# WIXIE.net
KiCad netlist of a schematic drawn in EAGLE
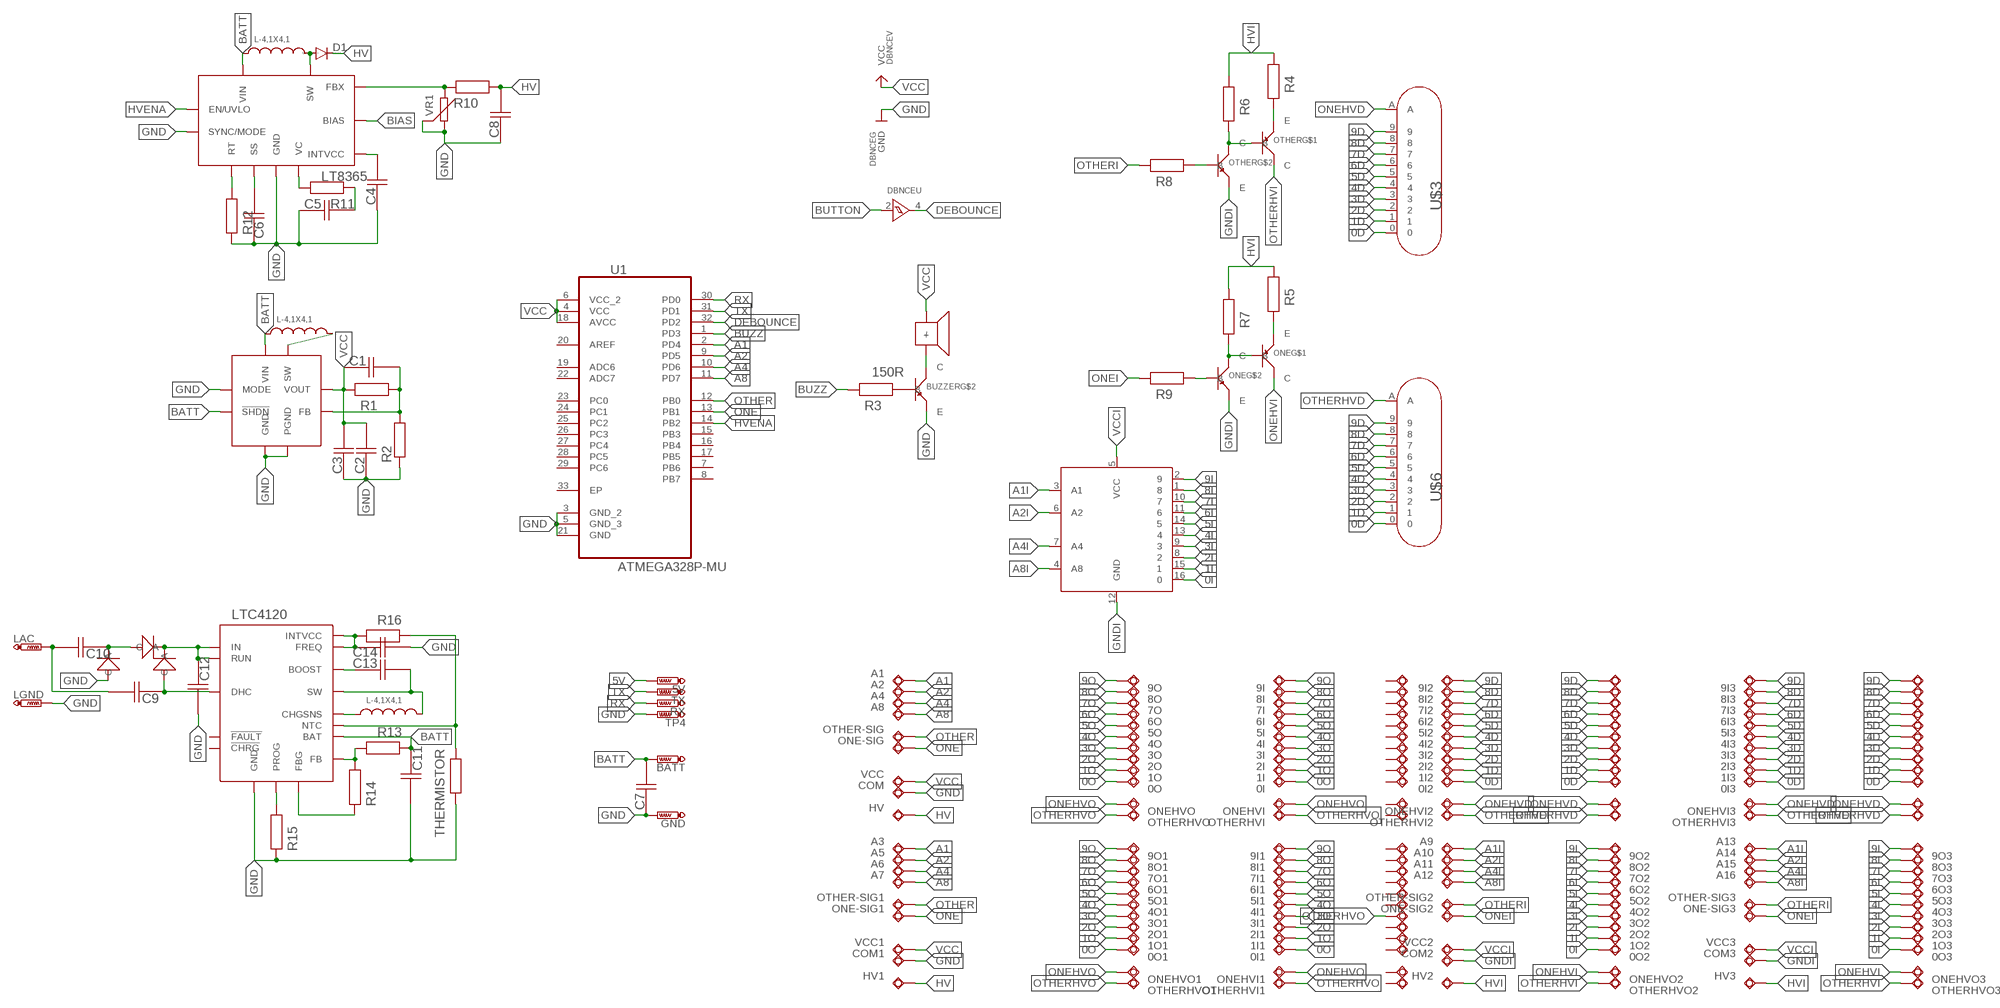
[diagram p0: schematic, sheet 1]

(export (version "E")
  (design (tool "Eeschema 10.0.6"))
  (components
    (comp (ref "0I")
      (value "TPSQTP12SQ")
      (footprint "eagle-import:TP12SQ")
      (libsource (lib "eagle-import") (part "TPSQTP12SQ"))
    )
    (comp (ref "0I1")
      (value "TPSQTP12SQ")
      (footprint "eagle-import:TP12SQ")
      (libsource (lib "eagle-import") (part "TPSQTP12SQ"))
    )
    (comp (ref "0I2")
      (value "TPSQTP12SQ")
      (footprint "eagle-import:TP12SQ")
      (libsource (lib "eagle-import") (part "TPSQTP12SQ"))
    )
    (comp (ref "0I3")
      (value "TPSQTP12SQ")
      (footprint "eagle-import:TP12SQ")
      (libsource (lib "eagle-import") (part "TPSQTP12SQ"))
    )
    (comp (ref "0O")
      (value "TPSQTP12SQ")
      (footprint "eagle-import:TP12SQ")
      (libsource (lib "eagle-import") (part "TPSQTP12SQ"))
    )
    (comp (ref "0O1")
      (value "TPSQTP12SQ")
      (footprint "eagle-import:TP12SQ")
      (libsource (lib "eagle-import") (part "TPSQTP12SQ"))
    )
    (comp (ref "0O2")
      (value "TPSQTP12SQ")
      (footprint "eagle-import:TP12SQ")
      (libsource (lib "eagle-import") (part "TPSQTP12SQ"))
    )
    (comp (ref "0O3")
      (value "TPSQTP12SQ")
      (footprint "eagle-import:TP12SQ")
      (libsource (lib "eagle-import") (part "TPSQTP12SQ"))
    )
    (comp (ref "1I")
      (value "TPSQTP12SQ")
      (footprint "eagle-import:TP12SQ")
      (libsource (lib "eagle-import") (part "TPSQTP12SQ"))
    )
    (comp (ref "1I1")
      (value "TPSQTP12SQ")
      (footprint "eagle-import:TP12SQ")
      (libsource (lib "eagle-import") (part "TPSQTP12SQ"))
    )
    (comp (ref "1I2")
      (value "TPSQTP12SQ")
      (footprint "eagle-import:TP12SQ")
      (libsource (lib "eagle-import") (part "TPSQTP12SQ"))
    )
    (comp (ref "1I3")
      (value "TPSQTP12SQ")
      (footprint "eagle-import:TP12SQ")
      (libsource (lib "eagle-import") (part "TPSQTP12SQ"))
    )
    (comp (ref "1O")
      (value "TPSQTP12SQ")
      (footprint "eagle-import:TP12SQ")
      (libsource (lib "eagle-import") (part "TPSQTP12SQ"))
    )
    (comp (ref "1O1")
      (value "TPSQTP12SQ")
      (footprint "eagle-import:TP12SQ")
      (libsource (lib "eagle-import") (part "TPSQTP12SQ"))
    )
    (comp (ref "1O2")
      (value "TPSQTP12SQ")
      (footprint "eagle-import:TP12SQ")
      (libsource (lib "eagle-import") (part "TPSQTP12SQ"))
    )
    (comp (ref "1O3")
      (value "TPSQTP12SQ")
      (footprint "eagle-import:TP12SQ")
      (libsource (lib "eagle-import") (part "TPSQTP12SQ"))
    )
    (comp (ref "2I")
      (value "TPSQTP12SQ")
      (footprint "eagle-import:TP12SQ")
      (libsource (lib "eagle-import") (part "TPSQTP12SQ"))
    )
    (comp (ref "2I1")
      (value "TPSQTP12SQ")
      (footprint "eagle-import:TP12SQ")
      (libsource (lib "eagle-import") (part "TPSQTP12SQ"))
    )
    (comp (ref "2I2")
      (value "TPSQTP12SQ")
      (footprint "eagle-import:TP12SQ")
      (libsource (lib "eagle-import") (part "TPSQTP12SQ"))
    )
    (comp (ref "2I3")
      (value "TPSQTP12SQ")
      (footprint "eagle-import:TP12SQ")
      (libsource (lib "eagle-import") (part "TPSQTP12SQ"))
    )
    (comp (ref "2O")
      (value "TPSQTP12SQ")
      (footprint "eagle-import:TP12SQ")
      (libsource (lib "eagle-import") (part "TPSQTP12SQ"))
    )
    (comp (ref "2O1")
      (value "TPSQTP12SQ")
      (footprint "eagle-import:TP12SQ")
      (libsource (lib "eagle-import") (part "TPSQTP12SQ"))
    )
    (comp (ref "2O2")
      (value "TPSQTP12SQ")
      (footprint "eagle-import:TP12SQ")
      (libsource (lib "eagle-import") (part "TPSQTP12SQ"))
    )
    (comp (ref "2O3")
      (value "TPSQTP12SQ")
      (footprint "eagle-import:TP12SQ")
      (libsource (lib "eagle-import") (part "TPSQTP12SQ"))
    )
    (comp (ref "3I")
      (value "TPSQTP12SQ")
      (footprint "eagle-import:TP12SQ")
      (libsource (lib "eagle-import") (part "TPSQTP12SQ"))
    )
    (comp (ref "3I1")
      (value "TPSQTP12SQ")
      (footprint "eagle-import:TP12SQ")
      (libsource (lib "eagle-import") (part "TPSQTP12SQ"))
    )
    (comp (ref "3I2")
      (value "TPSQTP12SQ")
      (footprint "eagle-import:TP12SQ")
      (libsource (lib "eagle-import") (part "TPSQTP12SQ"))
    )
    (comp (ref "3I3")
      (value "TPSQTP12SQ")
      (footprint "eagle-import:TP12SQ")
      (libsource (lib "eagle-import") (part "TPSQTP12SQ"))
    )
    (comp (ref "3O")
      (value "TPSQTP12SQ")
      (footprint "eagle-import:TP12SQ")
      (libsource (lib "eagle-import") (part "TPSQTP12SQ"))
    )
    (comp (ref "3O1")
      (value "TPSQTP12SQ")
      (footprint "eagle-import:TP12SQ")
      (libsource (lib "eagle-import") (part "TPSQTP12SQ"))
    )
    (comp (ref "3O2")
      (value "TPSQTP12SQ")
      (footprint "eagle-import:TP12SQ")
      (libsource (lib "eagle-import") (part "TPSQTP12SQ"))
    )
    (comp (ref "3O3")
      (value "TPSQTP12SQ")
      (footprint "eagle-import:TP12SQ")
      (libsource (lib "eagle-import") (part "TPSQTP12SQ"))
    )
    (comp (ref "4I")
      (value "TPSQTP12SQ")
      (footprint "eagle-import:TP12SQ")
      (libsource (lib "eagle-import") (part "TPSQTP12SQ"))
    )
    (comp (ref "4I1")
      (value "TPSQTP12SQ")
      (footprint "eagle-import:TP12SQ")
      (libsource (lib "eagle-import") (part "TPSQTP12SQ"))
    )
    (comp (ref "4I2")
      (value "TPSQTP12SQ")
      (footprint "eagle-import:TP12SQ")
      (libsource (lib "eagle-import") (part "TPSQTP12SQ"))
    )
    (comp (ref "4I3")
      (value "TPSQTP12SQ")
      (footprint "eagle-import:TP12SQ")
      (libsource (lib "eagle-import") (part "TPSQTP12SQ"))
    )
    (comp (ref "4O")
      (value "TPSQTP12SQ")
      (footprint "eagle-import:TP12SQ")
      (libsource (lib "eagle-import") (part "TPSQTP12SQ"))
    )
    (comp (ref "4O1")
      (value "TPSQTP12SQ")
      (footprint "eagle-import:TP12SQ")
      (libsource (lib "eagle-import") (part "TPSQTP12SQ"))
    )
    (comp (ref "4O2")
      (value "TPSQTP12SQ")
      (footprint "eagle-import:TP12SQ")
      (libsource (lib "eagle-import") (part "TPSQTP12SQ"))
    )
    (comp (ref "4O3")
      (value "TPSQTP12SQ")
      (footprint "eagle-import:TP12SQ")
      (libsource (lib "eagle-import") (part "TPSQTP12SQ"))
    )
    (comp (ref "5I")
      (value "TPSQTP12SQ")
      (footprint "eagle-import:TP12SQ")
      (libsource (lib "eagle-import") (part "TPSQTP12SQ"))
    )
    (comp (ref "5I1")
      (value "TPSQTP12SQ")
      (footprint "eagle-import:TP12SQ")
      (libsource (lib "eagle-import") (part "TPSQTP12SQ"))
    )
    (comp (ref "5I2")
      (value "TPSQTP12SQ")
      (footprint "eagle-import:TP12SQ")
      (libsource (lib "eagle-import") (part "TPSQTP12SQ"))
    )
    (comp (ref "5I3")
      (value "TPSQTP12SQ")
      (footprint "eagle-import:TP12SQ")
      (libsource (lib "eagle-import") (part "TPSQTP12SQ"))
    )
    (comp (ref "5O")
      (value "TPSQTP12SQ")
      (footprint "eagle-import:TP12SQ")
      (libsource (lib "eagle-import") (part "TPSQTP12SQ"))
    )
    (comp (ref "5O1")
      (value "TPSQTP12SQ")
      (footprint "eagle-import:TP12SQ")
      (libsource (lib "eagle-import") (part "TPSQTP12SQ"))
    )
    (comp (ref "5O2")
      (value "TPSQTP12SQ")
      (footprint "eagle-import:TP12SQ")
      (libsource (lib "eagle-import") (part "TPSQTP12SQ"))
    )
    (comp (ref "5O3")
      (value "TPSQTP12SQ")
      (footprint "eagle-import:TP12SQ")
      (libsource (lib "eagle-import") (part "TPSQTP12SQ"))
    )
    (comp (ref "5V")
      (value "PTR1B1,27")
      (footprint "eagle-import:B1,27")
      (libsource (lib "eagle-import") (part "PTR1B1,27"))
    )
    (comp (ref "6I")
      (value "TPSQTP12SQ")
      (footprint "eagle-import:TP12SQ")
      (libsource (lib "eagle-import") (part "TPSQTP12SQ"))
    )
    (comp (ref "6I1")
      (value "TPSQTP12SQ")
      (footprint "eagle-import:TP12SQ")
      (libsource (lib "eagle-import") (part "TPSQTP12SQ"))
    )
    (comp (ref "6I2")
      (value "TPSQTP12SQ")
      (footprint "eagle-import:TP12SQ")
      (libsource (lib "eagle-import") (part "TPSQTP12SQ"))
    )
    (comp (ref "6I3")
      (value "TPSQTP12SQ")
      (footprint "eagle-import:TP12SQ")
      (libsource (lib "eagle-import") (part "TPSQTP12SQ"))
    )
    (comp (ref "6O")
      (value "TPSQTP12SQ")
      (footprint "eagle-import:TP12SQ")
      (libsource (lib "eagle-import") (part "TPSQTP12SQ"))
    )
    (comp (ref "6O1")
      (value "TPSQTP12SQ")
      (footprint "eagle-import:TP12SQ")
      (libsource (lib "eagle-import") (part "TPSQTP12SQ"))
    )
    (comp (ref "6O2")
      (value "TPSQTP12SQ")
      (footprint "eagle-import:TP12SQ")
      (libsource (lib "eagle-import") (part "TPSQTP12SQ"))
    )
    (comp (ref "6O3")
      (value "TPSQTP12SQ")
      (footprint "eagle-import:TP12SQ")
      (libsource (lib "eagle-import") (part "TPSQTP12SQ"))
    )
    (comp (ref "7I")
      (value "TPSQTP12SQ")
      (footprint "eagle-import:TP12SQ")
      (libsource (lib "eagle-import") (part "TPSQTP12SQ"))
    )
    (comp (ref "7I1")
      (value "TPSQTP12SQ")
      (footprint "eagle-import:TP12SQ")
      (libsource (lib "eagle-import") (part "TPSQTP12SQ"))
    )
    (comp (ref "7I2")
      (value "TPSQTP12SQ")
      (footprint "eagle-import:TP12SQ")
      (libsource (lib "eagle-import") (part "TPSQTP12SQ"))
    )
    (comp (ref "7I3")
      (value "TPSQTP12SQ")
      (footprint "eagle-import:TP12SQ")
      (libsource (lib "eagle-import") (part "TPSQTP12SQ"))
    )
    (comp (ref "7O")
      (value "TPSQTP12SQ")
      (footprint "eagle-import:TP12SQ")
      (libsource (lib "eagle-import") (part "TPSQTP12SQ"))
    )
    (comp (ref "7O1")
      (value "TPSQTP12SQ")
      (footprint "eagle-import:TP12SQ")
      (libsource (lib "eagle-import") (part "TPSQTP12SQ"))
    )
    (comp (ref "7O2")
      (value "TPSQTP12SQ")
      (footprint "eagle-import:TP12SQ")
      (libsource (lib "eagle-import") (part "TPSQTP12SQ"))
    )
    (comp (ref "7O3")
      (value "TPSQTP12SQ")
      (footprint "eagle-import:TP12SQ")
      (libsource (lib "eagle-import") (part "TPSQTP12SQ"))
    )
    (comp (ref "8I")
      (value "TPSQTP12SQ")
      (footprint "eagle-import:TP12SQ")
      (libsource (lib "eagle-import") (part "TPSQTP12SQ"))
    )
    (comp (ref "8I1")
      (value "TPSQTP12SQ")
      (footprint "eagle-import:TP12SQ")
      (libsource (lib "eagle-import") (part "TPSQTP12SQ"))
    )
    (comp (ref "8I2")
      (value "TPSQTP12SQ")
      (footprint "eagle-import:TP12SQ")
      (libsource (lib "eagle-import") (part "TPSQTP12SQ"))
    )
    (comp (ref "8I3")
      (value "TPSQTP12SQ")
      (footprint "eagle-import:TP12SQ")
      (libsource (lib "eagle-import") (part "TPSQTP12SQ"))
    )
    (comp (ref "8O")
      (value "TPSQTP12SQ")
      (footprint "eagle-import:TP12SQ")
      (libsource (lib "eagle-import") (part "TPSQTP12SQ"))
    )
    (comp (ref "8O1")
      (value "TPSQTP12SQ")
      (footprint "eagle-import:TP12SQ")
      (libsource (lib "eagle-import") (part "TPSQTP12SQ"))
    )
    (comp (ref "8O2")
      (value "TPSQTP12SQ")
      (footprint "eagle-import:TP12SQ")
      (libsource (lib "eagle-import") (part "TPSQTP12SQ"))
    )
    (comp (ref "8O3")
      (value "TPSQTP12SQ")
      (footprint "eagle-import:TP12SQ")
      (libsource (lib "eagle-import") (part "TPSQTP12SQ"))
    )
    (comp (ref "9I")
      (value "TPSQTP12SQ")
      (footprint "eagle-import:TP12SQ")
      (libsource (lib "eagle-import") (part "TPSQTP12SQ"))
    )
    (comp (ref "9I1")
      (value "TPSQTP12SQ")
      (footprint "eagle-import:TP12SQ")
      (libsource (lib "eagle-import") (part "TPSQTP12SQ"))
    )
    (comp (ref "9I2")
      (value "TPSQTP12SQ")
      (footprint "eagle-import:TP12SQ")
      (libsource (lib "eagle-import") (part "TPSQTP12SQ"))
    )
    (comp (ref "9I3")
      (value "TPSQTP12SQ")
      (footprint "eagle-import:TP12SQ")
      (libsource (lib "eagle-import") (part "TPSQTP12SQ"))
    )
    (comp (ref "9O")
      (value "TPSQTP12SQ")
      (footprint "eagle-import:TP12SQ")
      (libsource (lib "eagle-import") (part "TPSQTP12SQ"))
    )
    (comp (ref "9O1")
      (value "TPSQTP12SQ")
      (footprint "eagle-import:TP12SQ")
      (libsource (lib "eagle-import") (part "TPSQTP12SQ"))
    )
    (comp (ref "9O2")
      (value "TPSQTP12SQ")
      (footprint "eagle-import:TP12SQ")
      (libsource (lib "eagle-import") (part "TPSQTP12SQ"))
    )
    (comp (ref "9O3")
      (value "TPSQTP12SQ")
      (footprint "eagle-import:TP12SQ")
      (libsource (lib "eagle-import") (part "TPSQTP12SQ"))
    )
    (comp (ref "A1")
      (value "TPSQTP12SQ")
      (footprint "eagle-import:TP12SQ")
      (libsource (lib "eagle-import") (part "TPSQTP12SQ"))
    )
    (comp (ref "A2")
      (value "TPSQTP12SQ")
      (footprint "eagle-import:TP12SQ")
      (libsource (lib "eagle-import") (part "TPSQTP12SQ"))
    )
    (comp (ref "A3")
      (value "TPSQTP12SQ")
      (footprint "eagle-import:TP12SQ")
      (libsource (lib "eagle-import") (part "TPSQTP12SQ"))
    )
    (comp (ref "A4")
      (value "TPSQTP12SQ")
      (footprint "eagle-import:TP12SQ")
      (libsource (lib "eagle-import") (part "TPSQTP12SQ"))
    )
    (comp (ref "A5")
      (value "TPSQTP12SQ")
      (footprint "eagle-import:TP12SQ")
      (libsource (lib "eagle-import") (part "TPSQTP12SQ"))
    )
    (comp (ref "A6")
      (value "TPSQTP12SQ")
      (footprint "eagle-import:TP12SQ")
      (libsource (lib "eagle-import") (part "TPSQTP12SQ"))
    )
    (comp (ref "A7")
      (value "TPSQTP12SQ")
      (footprint "eagle-import:TP12SQ")
      (libsource (lib "eagle-import") (part "TPSQTP12SQ"))
    )
    (comp (ref "A8")
      (value "TPSQTP12SQ")
      (footprint "eagle-import:TP12SQ")
      (libsource (lib "eagle-import") (part "TPSQTP12SQ"))
    )
    (comp (ref "A9")
      (value "TPSQTP12SQ")
      (footprint "eagle-import:TP12SQ")
      (libsource (lib "eagle-import") (part "TPSQTP12SQ"))
    )
    (comp (ref "A10")
      (value "TPSQTP12SQ")
      (footprint "eagle-import:TP12SQ")
      (libsource (lib "eagle-import") (part "TPSQTP12SQ"))
    )
    (comp (ref "A11")
      (value "TPSQTP12SQ")
      (footprint "eagle-import:TP12SQ")
      (libsource (lib "eagle-import") (part "TPSQTP12SQ"))
    )
    (comp (ref "A12")
      (value "TPSQTP12SQ")
      (footprint "eagle-import:TP12SQ")
      (libsource (lib "eagle-import") (part "TPSQTP12SQ"))
    )
    (comp (ref "A13")
      (value "TPSQTP12SQ")
      (footprint "eagle-import:TP12SQ")
      (libsource (lib "eagle-import") (part "TPSQTP12SQ"))
    )
    (comp (ref "A14")
      (value "TPSQTP12SQ")
      (footprint "eagle-import:TP12SQ")
      (libsource (lib "eagle-import") (part "TPSQTP12SQ"))
    )
    (comp (ref "A15")
      (value "TPSQTP12SQ")
      (footprint "eagle-import:TP12SQ")
      (libsource (lib "eagle-import") (part "TPSQTP12SQ"))
    )
    (comp (ref "A16")
      (value "TPSQTP12SQ")
      (footprint "eagle-import:TP12SQ")
      (libsource (lib "eagle-import") (part "TPSQTP12SQ"))
    )
    (comp (ref "BATT")
      (value "PTR1PAD1-13")
      (footprint "eagle-import:P1-13")
      (libsource (lib "eagle-import") (part "PTR1PAD1-13"))
    )
    (comp (ref "BUZZER")
      (value "MMDT5451")
      (footprint "eagle-import:SOT-363")
      (libsource (lib "eagle-import") (part "MMDT5451"))
    )
    (comp (ref "C1")
      (value "CAPACITOR-0603")
      (footprint "eagle-import:0603")
      (libsource (lib "eagle-import") (part "CAPACITOR-0603"))
    )
    (comp (ref "C2")
      (value "CAPACITOR-0603")
      (footprint "eagle-import:0603")
      (libsource (lib "eagle-import") (part "CAPACITOR-0603"))
    )
    (comp (ref "C3")
      (value "CAPACITOR-0603")
      (footprint "eagle-import:0603")
      (libsource (lib "eagle-import") (part "CAPACITOR-0603"))
    )
    (comp (ref "C4")
      (value "CAPACITOR-0603")
      (footprint "eagle-import:0603")
      (libsource (lib "eagle-import") (part "CAPACITOR-0603"))
    )
    (comp (ref "C5")
      (value "CAPACITOR-0603")
      (footprint "eagle-import:0603")
      (libsource (lib "eagle-import") (part "CAPACITOR-0603"))
    )
    (comp (ref "C6")
      (value "CAPACITOR-0603")
      (footprint "eagle-import:0603")
      (libsource (lib "eagle-import") (part "CAPACITOR-0603"))
    )
    (comp (ref "C7")
      (value "CAPACITOR-0603")
      (footprint "eagle-import:0603")
      (libsource (lib "eagle-import") (part "CAPACITOR-0603"))
    )
    (comp (ref "C8")
      (value "CAPACITOR-0603")
      (footprint "eagle-import:0603")
      (libsource (lib "eagle-import") (part "CAPACITOR-0603"))
    )
    (comp (ref "C9")
      (value "CAPACITOR-0603")
      (footprint "eagle-import:0603")
      (libsource (lib "eagle-import") (part "CAPACITOR-0603"))
    )
    (comp (ref "C10")
      (value "CAPACITOR-0603")
      (footprint "eagle-import:0603")
      (libsource (lib "eagle-import") (part "CAPACITOR-0603"))
    )
    (comp (ref "C11")
      (value "CAPACITOR-0603")
      (footprint "eagle-import:0603")
      (libsource (lib "eagle-import") (part "CAPACITOR-0603"))
    )
    (comp (ref "C12")
      (value "CAPACITOR-0603")
      (footprint "eagle-import:0603")
      (libsource (lib "eagle-import") (part "CAPACITOR-0603"))
    )
    (comp (ref "C13")
      (value "CAPACITOR-0603")
      (footprint "eagle-import:0603")
      (libsource (lib "eagle-import") (part "CAPACITOR-0603"))
    )
    (comp (ref "C14")
      (value "CAPACITOR-0603")
      (footprint "eagle-import:0603")
      (libsource (lib "eagle-import") (part "CAPACITOR-0603"))
    )
    (comp (ref "COM")
      (value "TPSQTP12SQ")
      (footprint "eagle-import:TP12SQ")
      (libsource (lib "eagle-import") (part "TPSQTP12SQ"))
    )
    (comp (ref "COM1")
      (value "TPSQTP12SQ")
      (footprint "eagle-import:TP12SQ")
      (libsource (lib "eagle-import") (part "TPSQTP12SQ"))
    )
    (comp (ref "COM2")
      (value "TPSQTP12SQ")
      (footprint "eagle-import:TP12SQ")
      (libsource (lib "eagle-import") (part "TPSQTP12SQ"))
    )
    (comp (ref "COM3")
      (value "TPSQTP12SQ")
      (footprint "eagle-import:TP12SQ")
      (libsource (lib "eagle-import") (part "TPSQTP12SQ"))
    )
    (comp (ref "D1")
      (value "DIODE-SOD123")
      (footprint "eagle-import:SOD123")
      (libsource (lib "eagle-import") (part "DIODE-SOD123"))
    )
    (comp (ref "DBNCE")
      (value "74AHC1G17")
      (footprint "eagle-import:SOT-353-1")
      (libsource (lib "eagle-import") (part "74AHC1G17"))
    )
    (comp (ref "GND")
      (value "PTR1PAD1-13")
      (footprint "eagle-import:P1-13")
      (libsource (lib "eagle-import") (part "PTR1PAD1-13"))
    )
    (comp (ref "HV")
      (value "TPSQTP12SQ")
      (footprint "eagle-import:TP12SQ")
      (libsource (lib "eagle-import") (part "TPSQTP12SQ"))
    )
    (comp (ref "HV1")
      (value "TPSQTP12SQ")
      (footprint "eagle-import:TP12SQ")
      (libsource (lib "eagle-import") (part "TPSQTP12SQ"))
    )
    (comp (ref "HV2")
      (value "TPSQTP12SQ")
      (footprint "eagle-import:TP12SQ")
      (libsource (lib "eagle-import") (part "TPSQTP12SQ"))
    )
    (comp (ref "HV3")
      (value "TPSQTP12SQ")
      (footprint "eagle-import:TP12SQ")
      (libsource (lib "eagle-import") (part "TPSQTP12SQ"))
    )
    (comp (ref "LAC")
      (value "PTR1PAD1-13")
      (footprint "eagle-import:P1-13")
      (libsource (lib "eagle-import") (part "PTR1PAD1-13"))
    )
    (comp (ref "LGND")
      (value "PTR1PAD1-13")
      (footprint "eagle-import:P1-13")
      (libsource (lib "eagle-import") (part "PTR1PAD1-13"))
    )
    (comp (ref "LT8365")
      (value "LT8365")
      (footprint "eagle-import:MSE16")
      (libsource (lib "eagle-import") (part "LT8365"))
    )
    (comp (ref "LTC3539")
      (value "LTC3539")
      (footprint "eagle-import:DFN8-2X3")
      (libsource (lib "eagle-import") (part "LTC3539"))
    )
    (comp (ref "LTC4120")
      (value "LTC4120")
      (footprint "eagle-import:QFN16")
      (libsource (lib "eagle-import") (part "LTC4120"))
    )
    (comp (ref "ONE")
      (value "MMDT5451")
      (footprint "eagle-import:SOT-363")
      (libsource (lib "eagle-import") (part "MMDT5451"))
    )
    (comp (ref "ONE-SIG")
      (value "TPSQTP12SQ")
      (footprint "eagle-import:TP12SQ")
      (libsource (lib "eagle-import") (part "TPSQTP12SQ"))
    )
    (comp (ref "ONE-SIG1")
      (value "TPSQTP12SQ")
      (footprint "eagle-import:TP12SQ")
      (libsource (lib "eagle-import") (part "TPSQTP12SQ"))
    )
    (comp (ref "ONE-SIG2")
      (value "TPSQTP12SQ")
      (footprint "eagle-import:TP12SQ")
      (libsource (lib "eagle-import") (part "TPSQTP12SQ"))
    )
    (comp (ref "ONE-SIG3")
      (value "TPSQTP12SQ")
      (footprint "eagle-import:TP12SQ")
      (libsource (lib "eagle-import") (part "TPSQTP12SQ"))
    )
    (comp (ref "ONEHVI")
      (value "TPSQTP12SQ")
      (footprint "eagle-import:TP12SQ")
      (libsource (lib "eagle-import") (part "TPSQTP12SQ"))
    )
    (comp (ref "ONEHVI1")
      (value "TPSQTP12SQ")
      (footprint "eagle-import:TP12SQ")
      (libsource (lib "eagle-import") (part "TPSQTP12SQ"))
    )
    (comp (ref "ONEHVI2")
      (value "TPSQTP12SQ")
      (footprint "eagle-import:TP12SQ")
      (libsource (lib "eagle-import") (part "TPSQTP12SQ"))
    )
    (comp (ref "ONEHVI3")
      (value "TPSQTP12SQ")
      (footprint "eagle-import:TP12SQ")
      (libsource (lib "eagle-import") (part "TPSQTP12SQ"))
    )
    (comp (ref "ONEHVO")
      (value "TPSQTP12SQ")
      (footprint "eagle-import:TP12SQ")
      (libsource (lib "eagle-import") (part "TPSQTP12SQ"))
    )
    (comp (ref "ONEHVO1")
      (value "TPSQTP12SQ")
      (footprint "eagle-import:TP12SQ")
      (libsource (lib "eagle-import") (part "TPSQTP12SQ"))
    )
    (comp (ref "ONEHVO2")
      (value "TPSQTP12SQ")
      (footprint "eagle-import:TP12SQ")
      (libsource (lib "eagle-import") (part "TPSQTP12SQ"))
    )
    (comp (ref "ONEHVO3")
      (value "TPSQTP12SQ")
      (footprint "eagle-import:TP12SQ")
      (libsource (lib "eagle-import") (part "TPSQTP12SQ"))
    )
    (comp (ref "OTHER")
      (value "MMDT5451")
      (footprint "eagle-import:SOT-363")
      (libsource (lib "eagle-import") (part "MMDT5451"))
    )
    (comp (ref "OTHER-SIG")
      (value "TPSQTP12SQ")
      (footprint "eagle-import:TP12SQ")
      (libsource (lib "eagle-import") (part "TPSQTP12SQ"))
    )
    (comp (ref "OTHER-SIG1")
      (value "TPSQTP12SQ")
      (footprint "eagle-import:TP12SQ")
      (libsource (lib "eagle-import") (part "TPSQTP12SQ"))
    )
    (comp (ref "OTHER-SIG2")
      (value "TPSQTP12SQ")
      (footprint "eagle-import:TP12SQ")
      (libsource (lib "eagle-import") (part "TPSQTP12SQ"))
    )
    (comp (ref "OTHER-SIG3")
      (value "TPSQTP12SQ")
      (footprint "eagle-import:TP12SQ")
      (libsource (lib "eagle-import") (part "TPSQTP12SQ"))
    )
    (comp (ref "OTHERHVI")
      (value "TPSQTP12SQ")
      (footprint "eagle-import:TP12SQ")
      (libsource (lib "eagle-import") (part "TPSQTP12SQ"))
    )
    (comp (ref "OTHERHVI1")
      (value "TPSQTP12SQ")
      (footprint "eagle-import:TP12SQ")
      (libsource (lib "eagle-import") (part "TPSQTP12SQ"))
    )
    (comp (ref "OTHERHVI2")
      (value "TPSQTP12SQ")
      (footprint "eagle-import:TP12SQ")
      (libsource (lib "eagle-import") (part "TPSQTP12SQ"))
    )
    (comp (ref "OTHERHVI3")
      (value "TPSQTP12SQ")
      (footprint "eagle-import:TP12SQ")
      (libsource (lib "eagle-import") (part "TPSQTP12SQ"))
    )
    (comp (ref "OTHERHVO")
      (value "TPSQTP12SQ")
      (footprint "eagle-import:TP12SQ")
      (libsource (lib "eagle-import") (part "TPSQTP12SQ"))
    )
    (comp (ref "OTHERHVO1")
      (value "TPSQTP12SQ")
      (footprint "eagle-import:TP12SQ")
      (libsource (lib "eagle-import") (part "TPSQTP12SQ"))
    )
    (comp (ref "OTHERHVO2")
      (value "TPSQTP12SQ")
      (footprint "eagle-import:TP12SQ")
      (libsource (lib "eagle-import") (part "TPSQTP12SQ"))
    )
    (comp (ref "OTHERHVO3")
      (value "TPSQTP12SQ")
      (footprint "eagle-import:TP12SQ")
      (libsource (lib "eagle-import") (part "TPSQTP12SQ"))
    )
    (comp (ref "R1")
      (value "RESISTOR-0603")
      (footprint "eagle-import:0603")
      (libsource (lib "eagle-import") (part "RESISTOR-0603"))
    )
    (comp (ref "R2")
      (value "RESISTOR-0603")
      (footprint "eagle-import:0603")
      (libsource (lib "eagle-import") (part "RESISTOR-0603"))
    )
    (comp (ref "R3")
      (value "150R")
      (footprint "eagle-import:0603")
      (libsource (lib "eagle-import") (part "RESISTOR-0603"))
    )
    (comp (ref "R4")
      (value "RESISTOR-0603")
      (footprint "eagle-import:0603")
      (libsource (lib "eagle-import") (part "RESISTOR-0603"))
    )
    (comp (ref "R5")
      (value "RESISTOR-0603")
      (footprint "eagle-import:0603")
      (libsource (lib "eagle-import") (part "RESISTOR-0603"))
    )
    (comp (ref "R6")
      (value "RESISTOR-0603")
      (footprint "eagle-import:0603")
      (libsource (lib "eagle-import") (part "RESISTOR-0603"))
    )
    (comp (ref "R7")
      (value "RESISTOR-0603")
      (footprint "eagle-import:0603")
      (libsource (lib "eagle-import") (part "RESISTOR-0603"))
    )
    (comp (ref "R8")
      (value "RESISTOR-0603")
      (footprint "eagle-import:0603")
      (libsource (lib "eagle-import") (part "RESISTOR-0603"))
    )
    (comp (ref "R9")
      (value "RESISTOR-0603")
      (footprint "eagle-import:0603")
      (libsource (lib "eagle-import") (part "RESISTOR-0603"))
    )
    (comp (ref "R10")
      (value "RESISTOR-0603")
      (footprint "eagle-import:0603")
      (libsource (lib "eagle-import") (part "RESISTOR-0603"))
    )
    (comp (ref "R11")
      (value "RESISTOR-0603")
      (footprint "eagle-import:0603")
      (libsource (lib "eagle-import") (part "RESISTOR-0603"))
    )
    (comp (ref "R12")
      (value "RESISTOR-0603")
      (footprint "eagle-import:0603")
      (libsource (lib "eagle-import") (part "RESISTOR-0603"))
    )
    (comp (ref "R13")
      (value "RESISTOR-0603")
      (footprint "eagle-import:0603")
      (libsource (lib "eagle-import") (part "RESISTOR-0603"))
    )
    (comp (ref "R14")
      (value "RESISTOR-0603")
      (footprint "eagle-import:0603")
      (libsource (lib "eagle-import") (part "RESISTOR-0603"))
    )
    (comp (ref "R15")
      (value "RESISTOR-0603")
      (footprint "eagle-import:0603")
      (libsource (lib "eagle-import") (part "RESISTOR-0603"))
    )
    (comp (ref "R16")
      (value "RESISTOR-0603")
      (footprint "eagle-import:0603")
      (libsource (lib "eagle-import") (part "RESISTOR-0603"))
    )
    (comp (ref "RX")
      (value "PTR1B1,27")
      (footprint "eagle-import:B1,27")
      (libsource (lib "eagle-import") (part "PTR1B1,27"))
    )
    (comp (ref "THERMISTOR")
      (value "RESISTOR-0603")
      (footprint "eagle-import:0603")
      (libsource (lib "eagle-import") (part "RESISTOR-0603"))
    )
    (comp (ref "TP1")
      (value "TPSQTP12SQ")
      (footprint "eagle-import:TP12SQ")
      (libsource (lib "eagle-import") (part "TPSQTP12SQ"))
    )
    (comp (ref "TP2")
      (value "TPSQTP12SQ")
      (footprint "eagle-import:TP12SQ")
      (libsource (lib "eagle-import") (part "TPSQTP12SQ"))
    )
    (comp (ref "TP3")
      (value "TPSQTP12SQ")
      (footprint "eagle-import:TP12SQ")
      (libsource (lib "eagle-import") (part "TPSQTP12SQ"))
    )
    (comp (ref "TP4")
      (value "PTR1B1,27")
      (footprint "eagle-import:B1,27")
      (libsource (lib "eagle-import") (part "PTR1B1,27"))
    )
    (comp (ref "TP5")
      (value "TPSQTP12SQ")
      (footprint "eagle-import:TP12SQ")
      (libsource (lib "eagle-import") (part "TPSQTP12SQ"))
    )
    (comp (ref "TP6")
      (value "TPSQTP12SQ")
      (footprint "eagle-import:TP12SQ")
      (libsource (lib "eagle-import") (part "TPSQTP12SQ"))
    )
    (comp (ref "TP7")
      (value "TPSQTP12SQ")
      (footprint "eagle-import:TP12SQ")
      (libsource (lib "eagle-import") (part "TPSQTP12SQ"))
    )
    (comp (ref "TP8")
      (value "TPSQTP12SQ")
      (footprint "eagle-import:TP12SQ")
      (libsource (lib "eagle-import") (part "TPSQTP12SQ"))
    )
    (comp (ref "TP9")
      (value "TPSQTP12SQ")
      (footprint "eagle-import:TP12SQ")
      (libsource (lib "eagle-import") (part "TPSQTP12SQ"))
    )
    (comp (ref "TP10")
      (value "TPSQTP12SQ")
      (footprint "eagle-import:TP12SQ")
      (libsource (lib "eagle-import") (part "TPSQTP12SQ"))
    )
    (comp (ref "TP11")
      (value "TPSQTP12SQ")
      (footprint "eagle-import:TP12SQ")
      (libsource (lib "eagle-import") (part "TPSQTP12SQ"))
    )
    (comp (ref "TP12")
      (value "TPSQTP12SQ")
      (footprint "eagle-import:TP12SQ")
      (libsource (lib "eagle-import") (part "TPSQTP12SQ"))
    )
    (comp (ref "TP13")
      (value "TPSQTP12SQ")
      (footprint "eagle-import:TP12SQ")
      (libsource (lib "eagle-import") (part "TPSQTP12SQ"))
    )
    (comp (ref "TP14")
      (value "TPSQTP12SQ")
      (footprint "eagle-import:TP12SQ")
      (libsource (lib "eagle-import") (part "TPSQTP12SQ"))
    )
    (comp (ref "TP15")
      (value "TPSQTP12SQ")
      (footprint "eagle-import:TP12SQ")
      (libsource (lib "eagle-import") (part "TPSQTP12SQ"))
    )
    (comp (ref "TP16")
      (value "TPSQTP12SQ")
      (footprint "eagle-import:TP12SQ")
      (libsource (lib "eagle-import") (part "TPSQTP12SQ"))
    )
    (comp (ref "TP17")
      (value "TPSQTP12SQ")
      (footprint "eagle-import:TP12SQ")
      (libsource (lib "eagle-import") (part "TPSQTP12SQ"))
    )
    (comp (ref "TP18")
      (value "TPSQTP12SQ")
      (footprint "eagle-import:TP12SQ")
      (libsource (lib "eagle-import") (part "TPSQTP12SQ"))
    )
    (comp (ref "TP19")
      (value "TPSQTP12SQ")
      (footprint "eagle-import:TP12SQ")
      (libsource (lib "eagle-import") (part "TPSQTP12SQ"))
    )
    (comp (ref "TP20")
      (value "TPSQTP12SQ")
      (footprint "eagle-import:TP12SQ")
      (libsource (lib "eagle-import") (part "TPSQTP12SQ"))
    )
    (comp (ref "TP21")
      (value "TPSQTP12SQ")
      (footprint "eagle-import:TP12SQ")
      (libsource (lib "eagle-import") (part "TPSQTP12SQ"))
    )
    (comp (ref "TP22")
      (value "TPSQTP12SQ")
      (footprint "eagle-import:TP12SQ")
      (libsource (lib "eagle-import") (part "TPSQTP12SQ"))
    )
    (comp (ref "TP23")
      (value "TPSQTP12SQ")
      (footprint "eagle-import:TP12SQ")
      (libsource (lib "eagle-import") (part "TPSQTP12SQ"))
    )
    (comp (ref "TP24")
      (value "TPSQTP12SQ")
      (footprint "eagle-import:TP12SQ")
      (libsource (lib "eagle-import") (part "TPSQTP12SQ"))
    )
    (comp (ref "TP25")
      (value "TPSQTP12SQ")
      (footprint "eagle-import:TP12SQ")
      (libsource (lib "eagle-import") (part "TPSQTP12SQ"))
    )
    (comp (ref "TP26")
      (value "TPSQTP12SQ")
      (footprint "eagle-import:TP12SQ")
      (libsource (lib "eagle-import") (part "TPSQTP12SQ"))
    )
    (comp (ref "TP27")
      (value "TPSQTP12SQ")
      (footprint "eagle-import:TP12SQ")
      (libsource (lib "eagle-import") (part "TPSQTP12SQ"))
    )
    (comp (ref "TP28")
      (value "TPSQTP12SQ")
      (footprint "eagle-import:TP12SQ")
      (libsource (lib "eagle-import") (part "TPSQTP12SQ"))
    )
    (comp (ref "TP29")
      (value "TPSQTP12SQ")
      (footprint "eagle-import:TP12SQ")
      (libsource (lib "eagle-import") (part "TPSQTP12SQ"))
    )
    (comp (ref "TP30")
      (value "TPSQTP12SQ")
      (footprint "eagle-import:TP12SQ")
      (libsource (lib "eagle-import") (part "TPSQTP12SQ"))
    )
    (comp (ref "TP31")
      (value "TPSQTP12SQ")
      (footprint "eagle-import:TP12SQ")
      (libsource (lib "eagle-import") (part "TPSQTP12SQ"))
    )
    (comp (ref "TP32")
      (value "TPSQTP12SQ")
      (footprint "eagle-import:TP12SQ")
      (libsource (lib "eagle-import") (part "TPSQTP12SQ"))
    )
    (comp (ref "TP33")
      (value "TPSQTP12SQ")
      (footprint "eagle-import:TP12SQ")
      (libsource (lib "eagle-import") (part "TPSQTP12SQ"))
    )
    (comp (ref "TP34")
      (value "TPSQTP12SQ")
      (footprint "eagle-import:TP12SQ")
      (libsource (lib "eagle-import") (part "TPSQTP12SQ"))
    )
    (comp (ref "TP35")
      (value "TPSQTP12SQ")
      (footprint "eagle-import:TP12SQ")
      (libsource (lib "eagle-import") (part "TPSQTP12SQ"))
    )
    (comp (ref "TP36")
      (value "TPSQTP12SQ")
      (footprint "eagle-import:TP12SQ")
      (libsource (lib "eagle-import") (part "TPSQTP12SQ"))
    )
    (comp (ref "TP37")
      (value "TPSQTP12SQ")
      (footprint "eagle-import:TP12SQ")
      (libsource (lib "eagle-import") (part "TPSQTP12SQ"))
    )
    (comp (ref "TP38")
      (value "TPSQTP12SQ")
      (footprint "eagle-import:TP12SQ")
      (libsource (lib "eagle-import") (part "TPSQTP12SQ"))
    )
    (comp (ref "TP39")
      (value "TPSQTP12SQ")
      (footprint "eagle-import:TP12SQ")
      (libsource (lib "eagle-import") (part "TPSQTP12SQ"))
    )
    (comp (ref "TP40")
      (value "TPSQTP12SQ")
      (footprint "eagle-import:TP12SQ")
      (libsource (lib "eagle-import") (part "TPSQTP12SQ"))
    )
    (comp (ref "TP41")
      (value "TPSQTP12SQ")
      (footprint "eagle-import:TP12SQ")
      (libsource (lib "eagle-import") (part "TPSQTP12SQ"))
    )
    (comp (ref "TP42")
      (value "TPSQTP12SQ")
      (footprint "eagle-import:TP12SQ")
      (libsource (lib "eagle-import") (part "TPSQTP12SQ"))
    )
    (comp (ref "TP43")
      (value "TPSQTP12SQ")
      (footprint "eagle-import:TP12SQ")
      (libsource (lib "eagle-import") (part "TPSQTP12SQ"))
    )
    (comp (ref "TP44")
      (value "TPSQTP12SQ")
      (footprint "eagle-import:TP12SQ")
      (libsource (lib "eagle-import") (part "TPSQTP12SQ"))
    )
    (comp (ref "TP45")
      (value "TPSQTP12SQ")
      (footprint "eagle-import:TP12SQ")
      (libsource (lib "eagle-import") (part "TPSQTP12SQ"))
    )
    (comp (ref "TP46")
      (value "TPSQTP12SQ")
      (footprint "eagle-import:TP12SQ")
      (libsource (lib "eagle-import") (part "TPSQTP12SQ"))
    )
    (comp (ref "TP47")
      (value "TPSQTP12SQ")
      (footprint "eagle-import:TP12SQ")
      (libsource (lib "eagle-import") (part "TPSQTP12SQ"))
    )
    (comp (ref "TP48")
      (value "TPSQTP12SQ")
      (footprint "eagle-import:TP12SQ")
      (libsource (lib "eagle-import") (part "TPSQTP12SQ"))
    )
    (comp (ref "TP49")
      (value "TPSQTP12SQ")
      (footprint "eagle-import:TP12SQ")
      (libsource (lib "eagle-import") (part "TPSQTP12SQ"))
    )
    (comp (ref "TX")
      (value "PTR1B1,27")
      (footprint "eagle-import:B1,27")
      (libsource (lib "eagle-import") (part "PTR1B1,27"))
    )
    (comp (ref "U$2")
      (value "BUZZ-8.5X8.5")
      (footprint "eagle-import:BUZZ-8.5X8.5")
      (libsource (lib "eagle-import") (part "BUZZ-8.5X8.5"))
    )
    (comp (ref "U$3")
      (value "IN-17")
      (footprint "eagle-import:IN-17")
      (libsource (lib "eagle-import") (part "IN-17"))
    )
    (comp (ref "U$5")
      (value "ZENER0603")
      (footprint "eagle-import:0603DIODE")
      (libsource (lib "eagle-import") (part "ZENER0603"))
    )
    (comp (ref "U$6")
      (value "IN-17")
      (footprint "eagle-import:IN-17")
      (libsource (lib "eagle-import") (part "IN-17"))
    )
    (comp (ref "U$7")
      (value "L-4,1X4,1")
      (footprint "eagle-import:L-4.1X4.1")
      (libsource (lib "eagle-import") (part "L-4,1X4,1"))
    )
    (comp (ref "U$8")
      (value "L-4,1X4,1")
      (footprint "eagle-import:L-4.1X4.1")
      (libsource (lib "eagle-import") (part "L-4,1X4,1"))
    )
    (comp (ref "U$9")
      (value "K133ID1")
      (footprint "eagle-import:K133ID1")
      (libsource (lib "eagle-import") (part "K133ID1"))
    )
    (comp (ref "U$10")
      (value "L-4,1X4,1")
      (footprint "eagle-import:L-4.1X4.1")
      (libsource (lib "eagle-import") (part "L-4,1X4,1"))
    )
    (comp (ref "U$11")
      (value "ZENER0603")
      (footprint "eagle-import:0603DIODE")
      (libsource (lib "eagle-import") (part "ZENER0603"))
    )
    (comp (ref "U$12")
      (value "ZENER0603")
      (footprint "eagle-import:0603DIODE")
      (libsource (lib "eagle-import") (part "ZENER0603"))
    )
    (comp (ref "U1")
      (value "ATMEGA328P-MU")
      (footprint "eagle-import:QFN50P500X500X100-33N")
      (libsource (lib "eagle-import") (part "ATMEGA328P-MU"))
    )
    (comp (ref "VCC")
      (value "TPSQTP12SQ")
      (footprint "eagle-import:TP12SQ")
      (libsource (lib "eagle-import") (part "TPSQTP12SQ"))
    )
    (comp (ref "VCC1")
      (value "TPSQTP12SQ")
      (footprint "eagle-import:TP12SQ")
      (libsource (lib "eagle-import") (part "TPSQTP12SQ"))
    )
    (comp (ref "VCC2")
      (value "TPSQTP12SQ")
      (footprint "eagle-import:TP12SQ")
      (libsource (lib "eagle-import") (part "TPSQTP12SQ"))
    )
    (comp (ref "VCC3")
      (value "TPSQTP12SQ")
      (footprint "eagle-import:TP12SQ")
      (libsource (lib "eagle-import") (part "TPSQTP12SQ"))
    )
    (comp (ref "VR1")
      (value "SR3305")
      (footprint "eagle-import:SR3305")
      (libsource (lib "eagle-import") (part "SR3305"))
    )
  )
  (nets
    (net (code "1") (name "0D") (class "Default")
      (node (ref "0I2") (pin "TP") (pinfunction "TP_TP") (pintype "input"))
      (node (ref "0I3") (pin "TP") (pinfunction "TP_TP") (pintype "input"))
      (node (ref "TP23") (pin "TP") (pinfunction "TP_TP") (pintype "input"))
      (node (ref "TP47") (pin "TP") (pinfunction "TP_TP") (pintype "input"))
      (node (ref "U$3") (pin "0") (pinfunction "0_0") (pintype "bidirectional"))
      (node (ref "U$6") (pin "0") (pinfunction "0_0") (pintype "bidirectional"))
    )
    (net (code "2") (name "0I") (class "Default")
      (node (ref "0O2") (pin "TP") (pinfunction "TP_TP") (pintype "input"))
      (node (ref "0O3") (pin "TP") (pinfunction "TP_TP") (pintype "input"))
      (node (ref "U$9") (pin "16") (pinfunction "0_16") (pintype "bidirectional"))
    )
    (net (code "3") (name "0O") (class "Default")
      (node (ref "0I") (pin "TP") (pinfunction "TP_TP") (pintype "input"))
      (node (ref "0I1") (pin "TP") (pinfunction "TP_TP") (pintype "input"))
      (node (ref "0O") (pin "TP") (pinfunction "TP_TP") (pintype "input"))
      (node (ref "0O1") (pin "TP") (pinfunction "TP_TP") (pintype "input"))
    )
    (net (code "4") (name "1D") (class "Default")
      (node (ref "1I2") (pin "TP") (pinfunction "TP_TP") (pintype "input"))
      (node (ref "1I3") (pin "TP") (pinfunction "TP_TP") (pintype "input"))
      (node (ref "TP22") (pin "TP") (pinfunction "TP_TP") (pintype "input"))
      (node (ref "TP34") (pin "TP") (pinfunction "TP_TP") (pintype "input"))
      (node (ref "U$3") (pin "1") (pinfunction "1_1") (pintype "bidirectional"))
      (node (ref "U$6") (pin "1") (pinfunction "1_1") (pintype "bidirectional"))
    )
    (net (code "5") (name "1I") (class "Default")
      (node (ref "1O2") (pin "TP") (pinfunction "TP_TP") (pintype "input"))
      (node (ref "1O3") (pin "TP") (pinfunction "TP_TP") (pintype "input"))
      (node (ref "U$9") (pin "15") (pinfunction "1_15") (pintype "bidirectional"))
    )
    (net (code "6") (name "1O") (class "Default")
      (node (ref "1I") (pin "TP") (pinfunction "TP_TP") (pintype "input"))
      (node (ref "1I1") (pin "TP") (pinfunction "TP_TP") (pintype "input"))
      (node (ref "1O") (pin "TP") (pinfunction "TP_TP") (pintype "input"))
      (node (ref "1O1") (pin "TP") (pinfunction "TP_TP") (pintype "input"))
    )
    (net (code "7") (name "2D") (class "Default")
      (node (ref "2I2") (pin "TP") (pinfunction "TP_TP") (pintype "input"))
      (node (ref "2I3") (pin "TP") (pinfunction "TP_TP") (pintype "input"))
      (node (ref "TP21") (pin "TP") (pinfunction "TP_TP") (pintype "input"))
      (node (ref "TP33") (pin "TP") (pinfunction "TP_TP") (pintype "input"))
      (node (ref "U$3") (pin "2") (pinfunction "2_2") (pintype "bidirectional"))
      (node (ref "U$6") (pin "2") (pinfunction "2_2") (pintype "bidirectional"))
    )
    (net (code "8") (name "2I") (class "Default")
      (node (ref "2O2") (pin "TP") (pinfunction "TP_TP") (pintype "input"))
      (node (ref "2O3") (pin "TP") (pinfunction "TP_TP") (pintype "input"))
      (node (ref "U$9") (pin "8") (pinfunction "2_8") (pintype "bidirectional"))
    )
    (net (code "9") (name "2O") (class "Default")
      (node (ref "2I") (pin "TP") (pinfunction "TP_TP") (pintype "input"))
      (node (ref "2I1") (pin "TP") (pinfunction "TP_TP") (pintype "input"))
      (node (ref "2O") (pin "TP") (pinfunction "TP_TP") (pintype "input"))
      (node (ref "2O1") (pin "TP") (pinfunction "TP_TP") (pintype "input"))
    )
    (net (code "10") (name "3D") (class "Default")
      (node (ref "3I2") (pin "TP") (pinfunction "TP_TP") (pintype "input"))
      (node (ref "3I3") (pin "TP") (pinfunction "TP_TP") (pintype "input"))
      (node (ref "TP20") (pin "TP") (pinfunction "TP_TP") (pintype "input"))
      (node (ref "TP32") (pin "TP") (pinfunction "TP_TP") (pintype "input"))
      (node (ref "U$3") (pin "3") (pinfunction "3_3") (pintype "bidirectional"))
      (node (ref "U$6") (pin "3") (pinfunction "3_3") (pintype "bidirectional"))
    )
    (net (code "11") (name "3I") (class "Default")
      (node (ref "3O2") (pin "TP") (pinfunction "TP_TP") (pintype "input"))
      (node (ref "3O3") (pin "TP") (pinfunction "TP_TP") (pintype "input"))
      (node (ref "U$9") (pin "9") (pinfunction "3_9") (pintype "bidirectional"))
    )
    (net (code "12") (name "3O") (class "Default")
      (node (ref "3I") (pin "TP") (pinfunction "TP_TP") (pintype "input"))
      (node (ref "3I1") (pin "TP") (pinfunction "TP_TP") (pintype "input"))
      (node (ref "3O") (pin "TP") (pinfunction "TP_TP") (pintype "input"))
      (node (ref "3O1") (pin "TP") (pinfunction "TP_TP") (pintype "input"))
    )
    (net (code "13") (name "4D") (class "Default")
      (node (ref "4I2") (pin "TP") (pinfunction "TP_TP") (pintype "input"))
      (node (ref "4I3") (pin "TP") (pinfunction "TP_TP") (pintype "input"))
      (node (ref "TP19") (pin "TP") (pinfunction "TP_TP") (pintype "input"))
      (node (ref "TP31") (pin "TP") (pinfunction "TP_TP") (pintype "input"))
      (node (ref "U$3") (pin "4") (pinfunction "4_4") (pintype "bidirectional"))
      (node (ref "U$6") (pin "4") (pinfunction "4_4") (pintype "bidirectional"))
    )
    (net (code "14") (name "4I") (class "Default")
      (node (ref "4O2") (pin "TP") (pinfunction "TP_TP") (pintype "input"))
      (node (ref "4O3") (pin "TP") (pinfunction "TP_TP") (pintype "input"))
      (node (ref "U$9") (pin "13") (pinfunction "4_13") (pintype "bidirectional"))
    )
    (net (code "15") (name "4O") (class "Default")
      (node (ref "4I") (pin "TP") (pinfunction "TP_TP") (pintype "input"))
      (node (ref "4I1") (pin "TP") (pinfunction "TP_TP") (pintype "input"))
      (node (ref "4O") (pin "TP") (pinfunction "TP_TP") (pintype "input"))
      (node (ref "4O1") (pin "TP") (pinfunction "TP_TP") (pintype "input"))
    )
    (net (code "16") (name "5D") (class "Default")
      (node (ref "5I2") (pin "TP") (pinfunction "TP_TP") (pintype "input"))
      (node (ref "5I3") (pin "TP") (pinfunction "TP_TP") (pintype "input"))
      (node (ref "TP18") (pin "TP") (pinfunction "TP_TP") (pintype "input"))
      (node (ref "TP30") (pin "TP") (pinfunction "TP_TP") (pintype "input"))
      (node (ref "U$3") (pin "5") (pinfunction "5_5") (pintype "bidirectional"))
      (node (ref "U$6") (pin "5") (pinfunction "5_5") (pintype "bidirectional"))
    )
    (net (code "17") (name "5I") (class "Default")
      (node (ref "5O2") (pin "TP") (pinfunction "TP_TP") (pintype "input"))
      (node (ref "5O3") (pin "TP") (pinfunction "TP_TP") (pintype "input"))
      (node (ref "U$9") (pin "14") (pinfunction "5_14") (pintype "bidirectional"))
    )
    (net (code "18") (name "5O") (class "Default")
      (node (ref "5I") (pin "TP") (pinfunction "TP_TP") (pintype "input"))
      (node (ref "5I1") (pin "TP") (pinfunction "TP_TP") (pintype "input"))
      (node (ref "5O") (pin "TP") (pinfunction "TP_TP") (pintype "input"))
      (node (ref "5O1") (pin "TP") (pinfunction "TP_TP") (pintype "input"))
    )
    (net (code "19") (name "5V") (class "Default")
      (node (ref "5V") (pin "TP") (pinfunction "TP_TP") (pintype "input"))
    )
    (net (code "20") (name "6D") (class "Default")
      (node (ref "6I2") (pin "TP") (pinfunction "TP_TP") (pintype "input"))
      (node (ref "6I3") (pin "TP") (pinfunction "TP_TP") (pintype "input"))
      (node (ref "TP17") (pin "TP") (pinfunction "TP_TP") (pintype "input"))
      (node (ref "TP29") (pin "TP") (pinfunction "TP_TP") (pintype "input"))
      (node (ref "U$3") (pin "6") (pinfunction "6_6") (pintype "bidirectional"))
      (node (ref "U$6") (pin "6") (pinfunction "6_6") (pintype "bidirectional"))
    )
    (net (code "21") (name "6I") (class "Default")
      (node (ref "6O2") (pin "TP") (pinfunction "TP_TP") (pintype "input"))
      (node (ref "6O3") (pin "TP") (pinfunction "TP_TP") (pintype "input"))
      (node (ref "U$9") (pin "11") (pinfunction "6_11") (pintype "bidirectional"))
    )
    (net (code "22") (name "6O") (class "Default")
      (node (ref "6I") (pin "TP") (pinfunction "TP_TP") (pintype "input"))
      (node (ref "6I1") (pin "TP") (pinfunction "TP_TP") (pintype "input"))
      (node (ref "6O") (pin "TP") (pinfunction "TP_TP") (pintype "input"))
      (node (ref "6O1") (pin "TP") (pinfunction "TP_TP") (pintype "input"))
    )
    (net (code "23") (name "7D") (class "Default")
      (node (ref "7I2") (pin "TP") (pinfunction "TP_TP") (pintype "input"))
      (node (ref "7I3") (pin "TP") (pinfunction "TP_TP") (pintype "input"))
      (node (ref "TP16") (pin "TP") (pinfunction "TP_TP") (pintype "input"))
      (node (ref "TP28") (pin "TP") (pinfunction "TP_TP") (pintype "input"))
      (node (ref "U$3") (pin "7") (pinfunction "7_7") (pintype "bidirectional"))
      (node (ref "U$6") (pin "7") (pinfunction "7_7") (pintype "bidirectional"))
    )
    (net (code "24") (name "7I") (class "Default")
      (node (ref "7O2") (pin "TP") (pinfunction "TP_TP") (pintype "input"))
      (node (ref "7O3") (pin "TP") (pinfunction "TP_TP") (pintype "input"))
      (node (ref "U$9") (pin "10") (pinfunction "7_10") (pintype "bidirectional"))
    )
    (net (code "25") (name "7O") (class "Default")
      (node (ref "7I") (pin "TP") (pinfunction "TP_TP") (pintype "input"))
      (node (ref "7I1") (pin "TP") (pinfunction "TP_TP") (pintype "input"))
      (node (ref "7O") (pin "TP") (pinfunction "TP_TP") (pintype "input"))
      (node (ref "7O1") (pin "TP") (pinfunction "TP_TP") (pintype "input"))
    )
    (net (code "26") (name "8D") (class "Default")
      (node (ref "8I2") (pin "TP") (pinfunction "TP_TP") (pintype "input"))
      (node (ref "8I3") (pin "TP") (pinfunction "TP_TP") (pintype "input"))
      (node (ref "TP15") (pin "TP") (pinfunction "TP_TP") (pintype "input"))
      (node (ref "TP27") (pin "TP") (pinfunction "TP_TP") (pintype "input"))
      (node (ref "U$3") (pin "8") (pinfunction "8_8") (pintype "bidirectional"))
      (node (ref "U$6") (pin "8") (pinfunction "8_8") (pintype "bidirectional"))
    )
    (net (code "27") (name "8I") (class "Default")
      (node (ref "8O2") (pin "TP") (pinfunction "TP_TP") (pintype "input"))
      (node (ref "8O3") (pin "TP") (pinfunction "TP_TP") (pintype "input"))
      (node (ref "U$9") (pin "1") (pinfunction "8_1") (pintype "bidirectional"))
    )
    (net (code "28") (name "8O") (class "Default")
      (node (ref "8I") (pin "TP") (pinfunction "TP_TP") (pintype "input"))
      (node (ref "8I1") (pin "TP") (pinfunction "TP_TP") (pintype "input"))
      (node (ref "8O") (pin "TP") (pinfunction "TP_TP") (pintype "input"))
      (node (ref "8O1") (pin "TP") (pinfunction "TP_TP") (pintype "input"))
    )
    (net (code "29") (name "9D") (class "Default")
      (node (ref "9I2") (pin "TP") (pinfunction "TP_TP") (pintype "input"))
      (node (ref "9I3") (pin "TP") (pinfunction "TP_TP") (pintype "input"))
      (node (ref "TP14") (pin "TP") (pinfunction "TP_TP") (pintype "input"))
      (node (ref "TP26") (pin "TP") (pinfunction "TP_TP") (pintype "input"))
      (node (ref "U$3") (pin "9") (pinfunction "9_9") (pintype "bidirectional"))
      (node (ref "U$6") (pin "9") (pinfunction "9_9") (pintype "bidirectional"))
    )
    (net (code "30") (name "9I") (class "Default")
      (node (ref "9O2") (pin "TP") (pinfunction "TP_TP") (pintype "input"))
      (node (ref "9O3") (pin "TP") (pinfunction "TP_TP") (pintype "input"))
      (node (ref "U$9") (pin "2") (pinfunction "9_2") (pintype "bidirectional"))
    )
    (net (code "31") (name "9O") (class "Default")
      (node (ref "9I") (pin "TP") (pinfunction "TP_TP") (pintype "input"))
      (node (ref "9I1") (pin "TP") (pinfunction "TP_TP") (pintype "input"))
      (node (ref "9O") (pin "TP") (pinfunction "TP_TP") (pintype "input"))
      (node (ref "9O1") (pin "TP") (pinfunction "TP_TP") (pintype "input"))
    )
    (net (code "32") (name "A1") (class "Default")
      (node (ref "A1") (pin "TP") (pinfunction "TP_TP") (pintype "input"))
      (node (ref "A3") (pin "TP") (pinfunction "TP_TP") (pintype "input"))
      (node (ref "U1") (pin "2") (pinfunction "PD4_2") (pintype "bidirectional"))
    )
    (net (code "33") (name "A1I") (class "Default")
      (node (ref "A13") (pin "TP") (pinfunction "TP_TP") (pintype "input"))
      (node (ref "A9") (pin "TP") (pinfunction "TP_TP") (pintype "input"))
      (node (ref "U$9") (pin "3") (pinfunction "A1_3") (pintype "bidirectional"))
    )
    (net (code "34") (name "A2") (class "Default")
      (node (ref "A2") (pin "TP") (pinfunction "TP_TP") (pintype "input"))
      (node (ref "A5") (pin "TP") (pinfunction "TP_TP") (pintype "input"))
      (node (ref "U1") (pin "9") (pinfunction "PD5_9") (pintype "bidirectional"))
    )
    (net (code "35") (name "A2I") (class "Default")
      (node (ref "A10") (pin "TP") (pinfunction "TP_TP") (pintype "input"))
      (node (ref "A14") (pin "TP") (pinfunction "TP_TP") (pintype "input"))
      (node (ref "U$9") (pin "6") (pinfunction "A2_6") (pintype "bidirectional"))
    )
    (net (code "36") (name "A4") (class "Default")
      (node (ref "A4") (pin "TP") (pinfunction "TP_TP") (pintype "input"))
      (node (ref "A6") (pin "TP") (pinfunction "TP_TP") (pintype "input"))
      (node (ref "U1") (pin "10") (pinfunction "PD6_10") (pintype "bidirectional"))
    )
    (net (code "37") (name "A4I") (class "Default")
      (node (ref "A11") (pin "TP") (pinfunction "TP_TP") (pintype "input"))
      (node (ref "A15") (pin "TP") (pinfunction "TP_TP") (pintype "input"))
      (node (ref "U$9") (pin "7") (pinfunction "A4_7") (pintype "bidirectional"))
    )
    (net (code "38") (name "A8") (class "Default")
      (node (ref "A7") (pin "TP") (pinfunction "TP_TP") (pintype "input"))
      (node (ref "A8") (pin "TP") (pinfunction "TP_TP") (pintype "input"))
      (node (ref "U1") (pin "11") (pinfunction "PD7_11") (pintype "bidirectional"))
    )
    (net (code "39") (name "A8I") (class "Default")
      (node (ref "A12") (pin "TP") (pinfunction "TP_TP") (pintype "input"))
      (node (ref "A16") (pin "TP") (pinfunction "TP_TP") (pintype "input"))
      (node (ref "U$9") (pin "4") (pinfunction "A8_4") (pintype "bidirectional"))
    )
    (net (code "40") (name "BATT") (class "Default")
      (node (ref "BATT") (pin "TP") (pinfunction "TP_TP") (pintype "input"))
      (node (ref "C11") (pin "1") (pinfunction "P$1_1") (pintype "bidirectional"))
      (node (ref "C7") (pin "2") (pinfunction "P$2_2") (pintype "bidirectional"))
      (node (ref "LT8365") (pin "3") (pinfunction "VIN_3") (pintype "bidirectional"))
      (node (ref "LTC3539") (pin "4") (pinfunction "VIN_4") (pintype "bidirectional"))
      (node (ref "LTC3539") (pin "5") (pinfunction "~{SHDN}_5") (pintype "bidirectional"))
      (node (ref "LTC4120") (pin "09") (pinfunction "BAT_09") (pintype "bidirectional"))
      (node (ref "R13") (pin "1") (pinfunction "P$1_1") (pintype "bidirectional"))
      (node (ref "U$10") (pin "P$1") (pinfunction "P$1_P$1") (pintype "bidirectional"))
      (node (ref "U$8") (pin "P$1") (pinfunction "P$1_P$1") (pintype "bidirectional"))
    )
    (net (code "41") (name "BIAS") (class "Default")
      (node (ref "LT8365") (pin "7") (pinfunction "BIAS_7") (pintype "bidirectional"))
    )
    (net (code "42") (name "BUTTON") (class "Default")
      (node (ref "DBNCE") (pin "2") (pinfunction "A_2") (pintype "bidirectional"))
    )
    (net (code "43") (name "BUZZ") (class "Default")
      (node (ref "R3") (pin "1") (pinfunction "P$1_1") (pintype "bidirectional"))
      (node (ref "U1") (pin "1") (pinfunction "PD3_1") (pintype "bidirectional"))
    )
    (net (code "44") (name "DEBOUNCE") (class "Default")
      (node (ref "DBNCE") (pin "4") (pinfunction "Y_4") (pintype "bidirectional"))
      (node (ref "U1") (pin "32") (pinfunction "PD2_32") (pintype "bidirectional"))
    )
    (net (code "45") (name "GND") (class "Default")
      (node (ref "BUZZER") (pin "1") (pinfunction "E_1") (pintype "bidirectional"))
      (node (ref "C11") (pin "2") (pinfunction "P$2_2") (pintype "bidirectional"))
      (node (ref "C12") (pin "2") (pinfunction "P$2_2") (pintype "bidirectional"))
      (node (ref "C14") (pin "2") (pinfunction "P$2_2") (pintype "bidirectional"))
      (node (ref "C2") (pin "1") (pinfunction "P$1_1") (pintype "bidirectional"))
      (node (ref "C3") (pin "1") (pinfunction "P$1_1") (pintype "bidirectional"))
      (node (ref "C4") (pin "1") (pinfunction "P$1_1") (pintype "bidirectional"))
      (node (ref "C5") (pin "1") (pinfunction "P$1_1") (pintype "bidirectional"))
      (node (ref "C6") (pin "1") (pinfunction "P$1_1") (pintype "bidirectional"))
      (node (ref "C7") (pin "1") (pinfunction "P$1_1") (pintype "bidirectional"))
      (node (ref "C8") (pin "1") (pinfunction "P$1_1") (pintype "bidirectional"))
      (node (ref "COM") (pin "TP") (pinfunction "TP_TP") (pintype "input"))
      (node (ref "COM1") (pin "TP") (pinfunction "TP_TP") (pintype "input"))
      (node (ref "DBNCE") (pin "3") (pinfunction "GND_3") (pintype "bidirectional"))
      (node (ref "GND") (pin "TP") (pinfunction "TP_TP") (pintype "input"))
      (node (ref "LGND") (pin "TP") (pinfunction "TP_TP") (pintype "input"))
      (node (ref "LT8365") (pin "12") (pinfunction "SYNC/MODE_12") (pintype "bidirectional"))
      (node (ref "LT8365") (pin "PAD") (pinfunction "GND_PAD") (pintype "bidirectional"))
      (node (ref "LTC3539") (pin "2") (pinfunction "PGND_2") (pintype "bidirectional"))
      (node (ref "LTC3539") (pin "3") (pinfunction "GND_3") (pintype "bidirectional"))
      (node (ref "LTC3539") (pin "7") (pinfunction "MODE_7") (pintype "bidirectional"))
      (node (ref "LTC3539") (pin "PAD") (pinfunction "GND_PAD") (pintype "bidirectional"))
      (node (ref "LTC4120") (pin "05") (pinfunction "GND_05") (pintype "bidirectional"))
      (node (ref "R12") (pin "1") (pinfunction "P$1_1") (pintype "bidirectional"))
      (node (ref "R15") (pin "1") (pinfunction "P$1_1") (pintype "bidirectional"))
      (node (ref "R2") (pin "1") (pinfunction "P$1_1") (pintype "bidirectional"))
      (node (ref "THERMISTOR") (pin "2") (pinfunction "P$2_2") (pintype "bidirectional"))
      (node (ref "TP4") (pin "TP") (pinfunction "TP_TP") (pintype "input"))
      (node (ref "U$12") (pin "POS") (pinfunction "A_POS") (pintype "bidirectional"))
      (node (ref "U1") (pin "21") (pinfunction "GND_21") (pintype "passive"))
      (node (ref "U1") (pin "3") (pinfunction "GND_2_3") (pintype "passive"))
      (node (ref "U1") (pin "5") (pinfunction "GND_3_5") (pintype "passive"))
      (node (ref "VR1") (pin "2") (pinfunction "2_2") (pintype "bidirectional"))
      (node (ref "VR1") (pin "3") (pinfunction "3_3") (pintype "bidirectional"))
    )
    (net (code "46") (name "GNDI") (class "Default")
      (node (ref "COM2") (pin "TP") (pinfunction "TP_TP") (pintype "input"))
      (node (ref "COM3") (pin "TP") (pinfunction "TP_TP") (pintype "input"))
      (node (ref "ONE") (pin "1") (pinfunction "E_1") (pintype "bidirectional"))
      (node (ref "OTHER") (pin "1") (pinfunction "E_1") (pintype "bidirectional"))
      (node (ref "U$9") (pin "12") (pinfunction "GND_12") (pintype "bidirectional"))
    )
    (net (code "47") (name "HV") (class "Default")
      (node (ref "C8") (pin "2") (pinfunction "P$2_2") (pintype "bidirectional"))
      (node (ref "D1") (pin "C") (pinfunction "C_C") (pintype "passive"))
      (node (ref "HV") (pin "TP") (pinfunction "TP_TP") (pintype "input"))
      (node (ref "HV1") (pin "TP") (pinfunction "TP_TP") (pintype "input"))
      (node (ref "R10") (pin "2") (pinfunction "P$2_2") (pintype "bidirectional"))
    )
    (net (code "48") (name "HVENA") (class "Default")
      (node (ref "LT8365") (pin "1") (pinfunction "EN/UVLO_1") (pintype "bidirectional"))
      (node (ref "U1") (pin "14") (pinfunction "PB2_14") (pintype "bidirectional"))
    )
    (net (code "49") (name "HVI") (class "Default")
      (node (ref "HV2") (pin "TP") (pinfunction "TP_TP") (pintype "input"))
      (node (ref "HV3") (pin "TP") (pinfunction "TP_TP") (pintype "input"))
      (node (ref "R4") (pin "2") (pinfunction "P$2_2") (pintype "bidirectional"))
      (node (ref "R5") (pin "2") (pinfunction "P$2_2") (pintype "bidirectional"))
      (node (ref "R6") (pin "2") (pinfunction "P$2_2") (pintype "bidirectional"))
      (node (ref "R7") (pin "2") (pinfunction "P$2_2") (pintype "bidirectional"))
    )
    (net (code "50") (name "Net-(BUZZERB-B)") (class "Default")
      (node (ref "BUZZER") (pin "2") (pinfunction "B_2") (pintype "bidirectional"))
      (node (ref "R3") (pin "2") (pinfunction "P$2_2") (pintype "bidirectional"))
    )
    (net (code "51") (name "Net-(BUZZERB-C)") (class "Default")
      (node (ref "BUZZER") (pin "6") (pinfunction "C_6") (pintype "bidirectional"))
      (node (ref "U$2") (pin "-") (pinfunction "-_-") (pintype "bidirectional"))
    )
    (net (code "52") (name "Net-(C1-P$2)") (class "Default")
      (node (ref "C1") (pin "2") (pinfunction "P$2_2") (pintype "bidirectional"))
      (node (ref "LTC3539") (pin "6") (pinfunction "FB_6") (pintype "bidirectional"))
      (node (ref "R1") (pin "2") (pinfunction "P$2_2") (pintype "bidirectional"))
      (node (ref "R2") (pin "2") (pinfunction "P$2_2") (pintype "bidirectional"))
    )
    (net (code "53") (name "Net-(C4-P$2)") (class "Default")
      (node (ref "C4") (pin "2") (pinfunction "P$2_2") (pintype "bidirectional"))
      (node (ref "LT8365") (pin "5") (pinfunction "INTVCC_5") (pintype "bidirectional"))
    )
    (net (code "54") (name "Net-(C5-P$2)") (class "Default")
      (node (ref "C5") (pin "2") (pinfunction "P$2_2") (pintype "bidirectional"))
      (node (ref "R11") (pin "2") (pinfunction "P$2_2") (pintype "bidirectional"))
    )
    (net (code "55") (name "Net-(C6-P$2)") (class "Default")
      (node (ref "C6") (pin "2") (pinfunction "P$2_2") (pintype "bidirectional"))
      (node (ref "LT8365") (pin "11") (pinfunction "SS_11") (pintype "bidirectional"))
    )
    (net (code "56") (name "Net-(C9-P$1)") (class "Default")
      (node (ref "C9") (pin "1") (pinfunction "P$1_1") (pintype "bidirectional"))
      (node (ref "LTC4120") (pin "06") (pinfunction "DHC_06") (pintype "bidirectional"))
      (node (ref "U$11") (pin "POS") (pinfunction "A_POS") (pintype "bidirectional"))
    )
    (net (code "57") (name "Net-(C10-P$1)") (class "Default")
      (node (ref "C10") (pin "1") (pinfunction "P$1_1") (pintype "bidirectional"))
      (node (ref "U$12") (pin "NEG") (pinfunction "C_NEG") (pintype "bidirectional"))
      (node (ref "U$5") (pin "POS") (pinfunction "A_POS") (pintype "bidirectional"))
    )
    (net (code "58") (name "Net-(C10-P$2)") (class "Default")
      (node (ref "C10") (pin "2") (pinfunction "P$2_2") (pintype "bidirectional"))
      (node (ref "C9") (pin "2") (pinfunction "P$2_2") (pintype "bidirectional"))
      (node (ref "LAC") (pin "TP") (pinfunction "TP_TP") (pintype "input"))
    )
    (net (code "59") (name "Net-(C12-P$1)") (class "Default")
      (node (ref "C12") (pin "1") (pinfunction "P$1_1") (pintype "bidirectional"))
      (node (ref "LTC4120") (pin "03") (pinfunction "IN_03") (pintype "bidirectional"))
      (node (ref "LTC4120") (pin "16") (pinfunction "RUN_16") (pintype "bidirectional"))
      (node (ref "U$11") (pin "NEG") (pinfunction "C_NEG") (pintype "bidirectional"))
      (node (ref "U$5") (pin "NEG") (pinfunction "C_NEG") (pintype "bidirectional"))
    )
    (net (code "60") (name "Net-(C13-P$1)") (class "Default")
      (node (ref "C13") (pin "1") (pinfunction "P$1_1") (pintype "bidirectional"))
      (node (ref "LTC4120") (pin "02") (pinfunction "BOOST_02") (pintype "bidirectional"))
    )
    (net (code "61") (name "Net-(C13-P$2)") (class "Default")
      (node (ref "C13") (pin "2") (pinfunction "P$2_2") (pintype "bidirectional"))
      (node (ref "LTC4120") (pin "04") (pinfunction "SW_04") (pintype "bidirectional"))
      (node (ref "U$7") (pin "P$2") (pinfunction "P$2_P$2") (pintype "bidirectional"))
    )
    (net (code "62") (name "Net-(C14-P$1)") (class "Default")
      (node (ref "C14") (pin "1") (pinfunction "P$1_1") (pintype "bidirectional"))
      (node (ref "LTC4120") (pin "01") (pinfunction "INTVCC_01") (pintype "bidirectional"))
      (node (ref "LTC4120") (pin "07") (pinfunction "FREQ_07") (pintype "bidirectional"))
      (node (ref "R16") (pin "2") (pinfunction "P$2_2") (pintype "bidirectional"))
    )
    (net (code "63") (name "Net-(D1-PadA)") (class "Default")
      (node (ref "D1") (pin "A") (pinfunction "A_A") (pintype "passive"))
      (node (ref "LT8365") (pin "14") (pinfunction "SW_14") (pintype "bidirectional"))
      (node (ref "LT8365") (pin "16") (pinfunction "SW_16") (pintype "bidirectional"))
      (node (ref "U$8") (pin "P$2") (pinfunction "P$2_P$2") (pintype "bidirectional"))
    )
    (net (code "64") (name "Net-(LT8365-FBX)") (class "Default")
      (node (ref "LT8365") (pin "9") (pinfunction "FBX_9") (pintype "bidirectional"))
      (node (ref "R10") (pin "1") (pinfunction "P$1_1") (pintype "bidirectional"))
      (node (ref "VR1") (pin "1") (pinfunction "1_1") (pintype "bidirectional"))
    )
    (net (code "65") (name "Net-(LT8365-RT)") (class "Default")
      (node (ref "LT8365") (pin "10") (pinfunction "RT_10") (pintype "bidirectional"))
      (node (ref "R12") (pin "2") (pinfunction "P$2_2") (pintype "bidirectional"))
    )
    (net (code "66") (name "Net-(LT8365-VC)") (class "Default")
      (node (ref "LT8365") (pin "8") (pinfunction "VC_8") (pintype "bidirectional"))
      (node (ref "R11") (pin "1") (pinfunction "P$1_1") (pintype "bidirectional"))
    )
    (net (code "67") (name "Net-(LTC3539-SW)") (class "Default")
      (node (ref "LTC3539") (pin "1") (pinfunction "SW_1") (pintype "bidirectional"))
      (node (ref "U$10") (pin "P$2") (pinfunction "P$2_P$2") (pintype "bidirectional"))
    )
    (net (code "68") (name "Net-(LTC4120-CHGSNS)") (class "Default")
      (node (ref "LTC4120") (pin "08") (pinfunction "CHGSNS_08") (pintype "bidirectional"))
      (node (ref "U$7") (pin "P$1") (pinfunction "P$1_P$1") (pintype "bidirectional"))
    )
    (net (code "69") (name "Net-(LTC4120-FB)") (class "Default")
      (node (ref "LTC4120") (pin "10") (pinfunction "FB_10") (pintype "bidirectional"))
      (node (ref "R13") (pin "2") (pinfunction "P$2_2") (pintype "bidirectional"))
      (node (ref "R14") (pin "2") (pinfunction "P$2_2") (pintype "bidirectional"))
    )
    (net (code "70") (name "Net-(LTC4120-FBG)") (class "Default")
      (node (ref "LTC4120") (pin "11") (pinfunction "FBG_11") (pintype "bidirectional"))
      (node (ref "R14") (pin "1") (pinfunction "P$1_1") (pintype "bidirectional"))
    )
    (net (code "71") (name "Net-(LTC4120-NTC)") (class "Default")
      (node (ref "LTC4120") (pin "12") (pinfunction "NTC_12") (pintype "bidirectional"))
      (node (ref "R16") (pin "1") (pinfunction "P$1_1") (pintype "bidirectional"))
      (node (ref "THERMISTOR") (pin "1") (pinfunction "P$1_1") (pintype "bidirectional"))
    )
    (net (code "72") (name "Net-(LTC4120-PROG)") (class "Default")
      (node (ref "LTC4120") (pin "13") (pinfunction "PROG_13") (pintype "bidirectional"))
      (node (ref "R15") (pin "2") (pinfunction "P$2_2") (pintype "bidirectional"))
    )
    (net (code "73") (name "Net-(ONEA-B)") (class "Default")
      (node (ref "ONE") (pin "5") (pinfunction "B_5") (pintype "bidirectional"))
      (node (ref "ONE") (pin "6") (pinfunction "C_6") (pintype "bidirectional"))
      (node (ref "R7") (pin "1") (pinfunction "P$1_1") (pintype "bidirectional"))
    )
    (net (code "74") (name "Net-(ONEA-E)") (class "Default")
      (node (ref "ONE") (pin "4") (pinfunction "E_4") (pintype "bidirectional"))
      (node (ref "R5") (pin "1") (pinfunction "P$1_1") (pintype "bidirectional"))
    )
    (net (code "75") (name "Net-(ONEB-B)") (class "Default")
      (node (ref "ONE") (pin "2") (pinfunction "B_2") (pintype "bidirectional"))
      (node (ref "R9") (pin "2") (pinfunction "P$2_2") (pintype "bidirectional"))
    )
    (net (code "76") (name "Net-(OTHERA-B)") (class "Default")
      (node (ref "OTHER") (pin "5") (pinfunction "B_5") (pintype "bidirectional"))
      (node (ref "OTHER") (pin "6") (pinfunction "C_6") (pintype "bidirectional"))
      (node (ref "R6") (pin "1") (pinfunction "P$1_1") (pintype "bidirectional"))
    )
    (net (code "77") (name "Net-(OTHERA-E)") (class "Default")
      (node (ref "OTHER") (pin "4") (pinfunction "E_4") (pintype "bidirectional"))
      (node (ref "R4") (pin "1") (pinfunction "P$1_1") (pintype "bidirectional"))
    )
    (net (code "78") (name "Net-(OTHERB-B)") (class "Default")
      (node (ref "OTHER") (pin "2") (pinfunction "B_2") (pintype "bidirectional"))
      (node (ref "R8") (pin "2") (pinfunction "P$2_2") (pintype "bidirectional"))
    )
    (net (code "79") (name "ONE") (class "Default")
      (node (ref "ONE-SIG") (pin "TP") (pinfunction "TP_TP") (pintype "input"))
      (node (ref "ONE-SIG1") (pin "TP") (pinfunction "TP_TP") (pintype "input"))
      (node (ref "U1") (pin "13") (pinfunction "PB1_13") (pintype "bidirectional"))
    )
    (net (code "80") (name "ONEHVD") (class "Default")
      (node (ref "ONEHVI2") (pin "TP") (pinfunction "TP_TP") (pintype "input"))
      (node (ref "ONEHVI3") (pin "TP") (pinfunction "TP_TP") (pintype "input"))
      (node (ref "TP24") (pin "TP") (pinfunction "TP_TP") (pintype "input"))
      (node (ref "TP48") (pin "TP") (pinfunction "TP_TP") (pintype "input"))
      (node (ref "U$3") (pin "A") (pinfunction "A_A") (pintype "bidirectional"))
    )
    (net (code "81") (name "ONEHVI") (class "Default")
      (node (ref "ONE") (pin "3") (pinfunction "C_3") (pintype "bidirectional"))
      (node (ref "ONEHVO2") (pin "TP") (pinfunction "TP_TP") (pintype "input"))
      (node (ref "ONEHVO3") (pin "TP") (pinfunction "TP_TP") (pintype "input"))
    )
    (net (code "82") (name "ONEHVO") (class "Default")
      (node (ref "ONEHVI") (pin "TP") (pinfunction "TP_TP") (pintype "input"))
      (node (ref "ONEHVI1") (pin "TP") (pinfunction "TP_TP") (pintype "input"))
      (node (ref "ONEHVO") (pin "TP") (pinfunction "TP_TP") (pintype "input"))
      (node (ref "ONEHVO1") (pin "TP") (pinfunction "TP_TP") (pintype "input"))
    )
    (net (code "83") (name "ONEI") (class "Default")
      (node (ref "ONE-SIG2") (pin "TP") (pinfunction "TP_TP") (pintype "input"))
      (node (ref "ONE-SIG3") (pin "TP") (pinfunction "TP_TP") (pintype "input"))
      (node (ref "R9") (pin "1") (pinfunction "P$1_1") (pintype "bidirectional"))
    )
    (net (code "84") (name "OTHER") (class "Default")
      (node (ref "OTHER-SIG") (pin "TP") (pinfunction "TP_TP") (pintype "input"))
      (node (ref "OTHER-SIG1") (pin "TP") (pinfunction "TP_TP") (pintype "input"))
      (node (ref "U1") (pin "12") (pinfunction "PB0_12") (pintype "bidirectional"))
    )
    (net (code "85") (name "OTHERHVD") (class "Default")
      (node (ref "OTHERHVI2") (pin "TP") (pinfunction "TP_TP") (pintype "input"))
      (node (ref "OTHERHVI3") (pin "TP") (pinfunction "TP_TP") (pintype "input"))
      (node (ref "TP25") (pin "TP") (pinfunction "TP_TP") (pintype "input"))
      (node (ref "TP49") (pin "TP") (pinfunction "TP_TP") (pintype "input"))
      (node (ref "U$6") (pin "A") (pinfunction "A_A") (pintype "bidirectional"))
    )
    (net (code "86") (name "OTHERHVI") (class "Default")
      (node (ref "OTHER") (pin "3") (pinfunction "C_3") (pintype "bidirectional"))
      (node (ref "OTHERHVO2") (pin "TP") (pinfunction "TP_TP") (pintype "input"))
      (node (ref "OTHERHVO3") (pin "TP") (pinfunction "TP_TP") (pintype "input"))
    )
    (net (code "87") (name "OTHERHVO") (class "Default")
      (node (ref "OTHERHVI") (pin "TP") (pinfunction "TP_TP") (pintype "input"))
      (node (ref "OTHERHVI1") (pin "TP") (pinfunction "TP_TP") (pintype "input"))
      (node (ref "OTHERHVO") (pin "TP") (pinfunction "TP_TP") (pintype "input"))
      (node (ref "OTHERHVO1") (pin "TP") (pinfunction "TP_TP") (pintype "input"))
      (node (ref "TP8") (pin "TP") (pinfunction "TP_TP") (pintype "input"))
    )
    (net (code "88") (name "OTHERI") (class "Default")
      (node (ref "OTHER-SIG2") (pin "TP") (pinfunction "TP_TP") (pintype "input"))
      (node (ref "OTHER-SIG3") (pin "TP") (pinfunction "TP_TP") (pintype "input"))
      (node (ref "R8") (pin "1") (pinfunction "P$1_1") (pintype "bidirectional"))
    )
    (net (code "89") (name "RX") (class "Default")
      (node (ref "RX") (pin "TP") (pinfunction "TP_TP") (pintype "input"))
      (node (ref "U1") (pin "30") (pinfunction "PD0_30") (pintype "bidirectional"))
    )
    (net (code "90") (name "TX") (class "Default")
      (node (ref "TX") (pin "TP") (pinfunction "TP_TP") (pintype "input"))
      (node (ref "U1") (pin "31") (pinfunction "PD1_31") (pintype "bidirectional"))
    )
    (net (code "91") (name "VCC") (class "Default")
      (node (ref "C1") (pin "1") (pinfunction "P$1_1") (pintype "bidirectional"))
      (node (ref "C2") (pin "2") (pinfunction "P$2_2") (pintype "bidirectional"))
      (node (ref "C3") (pin "2") (pinfunction "P$2_2") (pintype "bidirectional"))
      (node (ref "DBNCE") (pin "5") (pinfunction "VCC_5") (pintype "bidirectional"))
      (node (ref "LTC3539") (pin "8") (pinfunction "VOUT_8") (pintype "bidirectional"))
      (node (ref "R1") (pin "1") (pinfunction "P$1_1") (pintype "bidirectional"))
      (node (ref "U$2") (pin "+") (pinfunction "+_+") (pintype "bidirectional"))
      (node (ref "U1") (pin "18") (pinfunction "AVCC_18") (pintype "power_in"))
      (node (ref "U1") (pin "4") (pinfunction "VCC_4") (pintype "power_in"))
      (node (ref "U1") (pin "6") (pinfunction "VCC_2_6") (pintype "power_in"))
      (node (ref "VCC") (pin "TP") (pinfunction "TP_TP") (pintype "input"))
      (node (ref "VCC1") (pin "TP") (pinfunction "TP_TP") (pintype "input"))
    )
    (net (code "92") (name "VCCI") (class "Default")
      (node (ref "U$9") (pin "5") (pinfunction "VCC_5") (pintype "bidirectional"))
      (node (ref "VCC2") (pin "TP") (pinfunction "TP_TP") (pintype "input"))
      (node (ref "VCC3") (pin "TP") (pinfunction "TP_TP") (pintype "input"))
    )
    (net (code "93") (name "unconnected-(LTC4120-~{CHRG}-Pad14)") (class "Default")
      (node (ref "LTC4120") (pin "14") (pinfunction "~{CHRG}_14") (pintype "bidirectional"))
    )
    (net (code "94") (name "unconnected-(LTC4120-~{FAULT}-Pad15)") (class "Default")
      (node (ref "LTC4120") (pin "15") (pinfunction "~{FAULT}_15") (pintype "bidirectional"))
    )
    (net (code "95") (name "unconnected-(TP1-PadTP)") (class "Default")
      (node (ref "TP1") (pin "TP") (pinfunction "TP_TP") (pintype "input"))
    )
    (net (code "96") (name "unconnected-(TP2-PadTP)") (class "Default")
      (node (ref "TP2") (pin "TP") (pinfunction "TP_TP") (pintype "input"))
    )
    (net (code "97") (name "unconnected-(TP3-PadTP)") (class "Default")
      (node (ref "TP3") (pin "TP") (pinfunction "TP_TP") (pintype "input"))
    )
    (net (code "98") (name "unconnected-(TP5-PadTP)") (class "Default")
      (node (ref "TP5") (pin "TP") (pinfunction "TP_TP") (pintype "input"))
    )
    (net (code "99") (name "unconnected-(TP6-PadTP)") (class "Default")
      (node (ref "TP6") (pin "TP") (pinfunction "TP_TP") (pintype "input"))
    )
    (net (code "100") (name "unconnected-(TP7-PadTP)") (class "Default")
      (node (ref "TP7") (pin "TP") (pinfunction "TP_TP") (pintype "input"))
    )
    (net (code "101") (name "unconnected-(TP9-PadTP)") (class "Default")
      (node (ref "TP9") (pin "TP") (pinfunction "TP_TP") (pintype "input"))
    )
    (net (code "102") (name "unconnected-(TP10-PadTP)") (class "Default")
      (node (ref "TP10") (pin "TP") (pinfunction "TP_TP") (pintype "input"))
    )
    (net (code "103") (name "unconnected-(TP11-PadTP)") (class "Default")
      (node (ref "TP11") (pin "TP") (pinfunction "TP_TP") (pintype "input"))
    )
    (net (code "104") (name "unconnected-(TP12-PadTP)") (class "Default")
      (node (ref "TP12") (pin "TP") (pinfunction "TP_TP") (pintype "input"))
    )
    (net (code "105") (name "unconnected-(TP13-PadTP)") (class "Default")
      (node (ref "TP13") (pin "TP") (pinfunction "TP_TP") (pintype "input"))
    )
    (net (code "106") (name "unconnected-(TP35-PadTP)") (class "Default")
      (node (ref "TP35") (pin "TP") (pinfunction "TP_TP") (pintype "input"))
    )
    (net (code "107") (name "unconnected-(TP36-PadTP)") (class "Default")
      (node (ref "TP36") (pin "TP") (pinfunction "TP_TP") (pintype "input"))
    )
    (net (code "108") (name "unconnected-(TP37-PadTP)") (class "Default")
      (node (ref "TP37") (pin "TP") (pinfunction "TP_TP") (pintype "input"))
    )
    (net (code "109") (name "unconnected-(TP38-PadTP)") (class "Default")
      (node (ref "TP38") (pin "TP") (pinfunction "TP_TP") (pintype "input"))
    )
    (net (code "110") (name "unconnected-(TP39-PadTP)") (class "Default")
      (node (ref "TP39") (pin "TP") (pinfunction "TP_TP") (pintype "input"))
    )
    (net (code "111") (name "unconnected-(TP40-PadTP)") (class "Default")
      (node (ref "TP40") (pin "TP") (pinfunction "TP_TP") (pintype "input"))
    )
    (net (code "112") (name "unconnected-(TP41-PadTP)") (class "Default")
      (node (ref "TP41") (pin "TP") (pinfunction "TP_TP") (pintype "input"))
    )
    (net (code "113") (name "unconnected-(TP42-PadTP)") (class "Default")
      (node (ref "TP42") (pin "TP") (pinfunction "TP_TP") (pintype "input"))
    )
    (net (code "114") (name "unconnected-(TP43-PadTP)") (class "Default")
      (node (ref "TP43") (pin "TP") (pinfunction "TP_TP") (pintype "input"))
    )
    (net (code "115") (name "unconnected-(TP44-PadTP)") (class "Default")
      (node (ref "TP44") (pin "TP") (pinfunction "TP_TP") (pintype "input"))
    )
    (net (code "116") (name "unconnected-(TP45-PadTP)") (class "Default")
      (node (ref "TP45") (pin "TP") (pinfunction "TP_TP") (pintype "input"))
    )
    (net (code "117") (name "unconnected-(TP46-PadTP)") (class "Default")
      (node (ref "TP46") (pin "TP") (pinfunction "TP_TP") (pintype "input"))
    )
    (net (code "118") (name "unconnected-(U1-ADC6-Pad19)") (class "Default")
      (node (ref "U1") (pin "19") (pinfunction "ADC6_19") (pintype "input"))
    )
    (net (code "119") (name "unconnected-(U1-ADC7-Pad22)") (class "Default")
      (node (ref "U1") (pin "22") (pinfunction "ADC7_22") (pintype "input"))
    )
    (net (code "120") (name "unconnected-(U1-AREF-Pad20)") (class "Default")
      (node (ref "U1") (pin "20") (pinfunction "AREF_20") (pintype "input"))
    )
    (net (code "121") (name "unconnected-(U1-EP-Pad33)") (class "Default")
      (node (ref "U1") (pin "33") (pinfunction "EP_33") (pintype "passive"))
    )
    (net (code "122") (name "unconnected-(U1-PB3-Pad15)") (class "Default")
      (node (ref "U1") (pin "15") (pinfunction "PB3_15") (pintype "bidirectional"))
    )
    (net (code "123") (name "unconnected-(U1-PB4-Pad16)") (class "Default")
      (node (ref "U1") (pin "16") (pinfunction "PB4_16") (pintype "bidirectional"))
    )
    (net (code "124") (name "unconnected-(U1-PB5-Pad17)") (class "Default")
      (node (ref "U1") (pin "17") (pinfunction "PB5_17") (pintype "bidirectional"))
    )
    (net (code "125") (name "unconnected-(U1-PB6-Pad7)") (class "Default")
      (node (ref "U1") (pin "7") (pinfunction "PB6_7") (pintype "bidirectional"))
    )
    (net (code "126") (name "unconnected-(U1-PB7-Pad8)") (class "Default")
      (node (ref "U1") (pin "8") (pinfunction "PB7_8") (pintype "bidirectional"))
    )
    (net (code "127") (name "unconnected-(U1-PC0-Pad23)") (class "Default")
      (node (ref "U1") (pin "23") (pinfunction "PC0_23") (pintype "bidirectional"))
    )
    (net (code "128") (name "unconnected-(U1-PC1-Pad24)") (class "Default")
      (node (ref "U1") (pin "24") (pinfunction "PC1_24") (pintype "bidirectional"))
    )
    (net (code "129") (name "unconnected-(U1-PC2-Pad25)") (class "Default")
      (node (ref "U1") (pin "25") (pinfunction "PC2_25") (pintype "bidirectional"))
    )
    (net (code "130") (name "unconnected-(U1-PC3-Pad26)") (class "Default")
      (node (ref "U1") (pin "26") (pinfunction "PC3_26") (pintype "bidirectional"))
    )
    (net (code "131") (name "unconnected-(U1-PC4-Pad27)") (class "Default")
      (node (ref "U1") (pin "27") (pinfunction "PC4_27") (pintype "bidirectional"))
    )
    (net (code "132") (name "unconnected-(U1-PC5-Pad28)") (class "Default")
      (node (ref "U1") (pin "28") (pinfunction "PC5_28") (pintype "bidirectional"))
    )
    (net (code "133") (name "unconnected-(U1-PC6-Pad29)") (class "Default")
      (node (ref "U1") (pin "29") (pinfunction "PC6_29") (pintype "bidirectional"))
    )
  )
)
